# Artemis_Charger_Mod_PCB_2.net
KiCad netlist of a schematic drawn in EAGLE
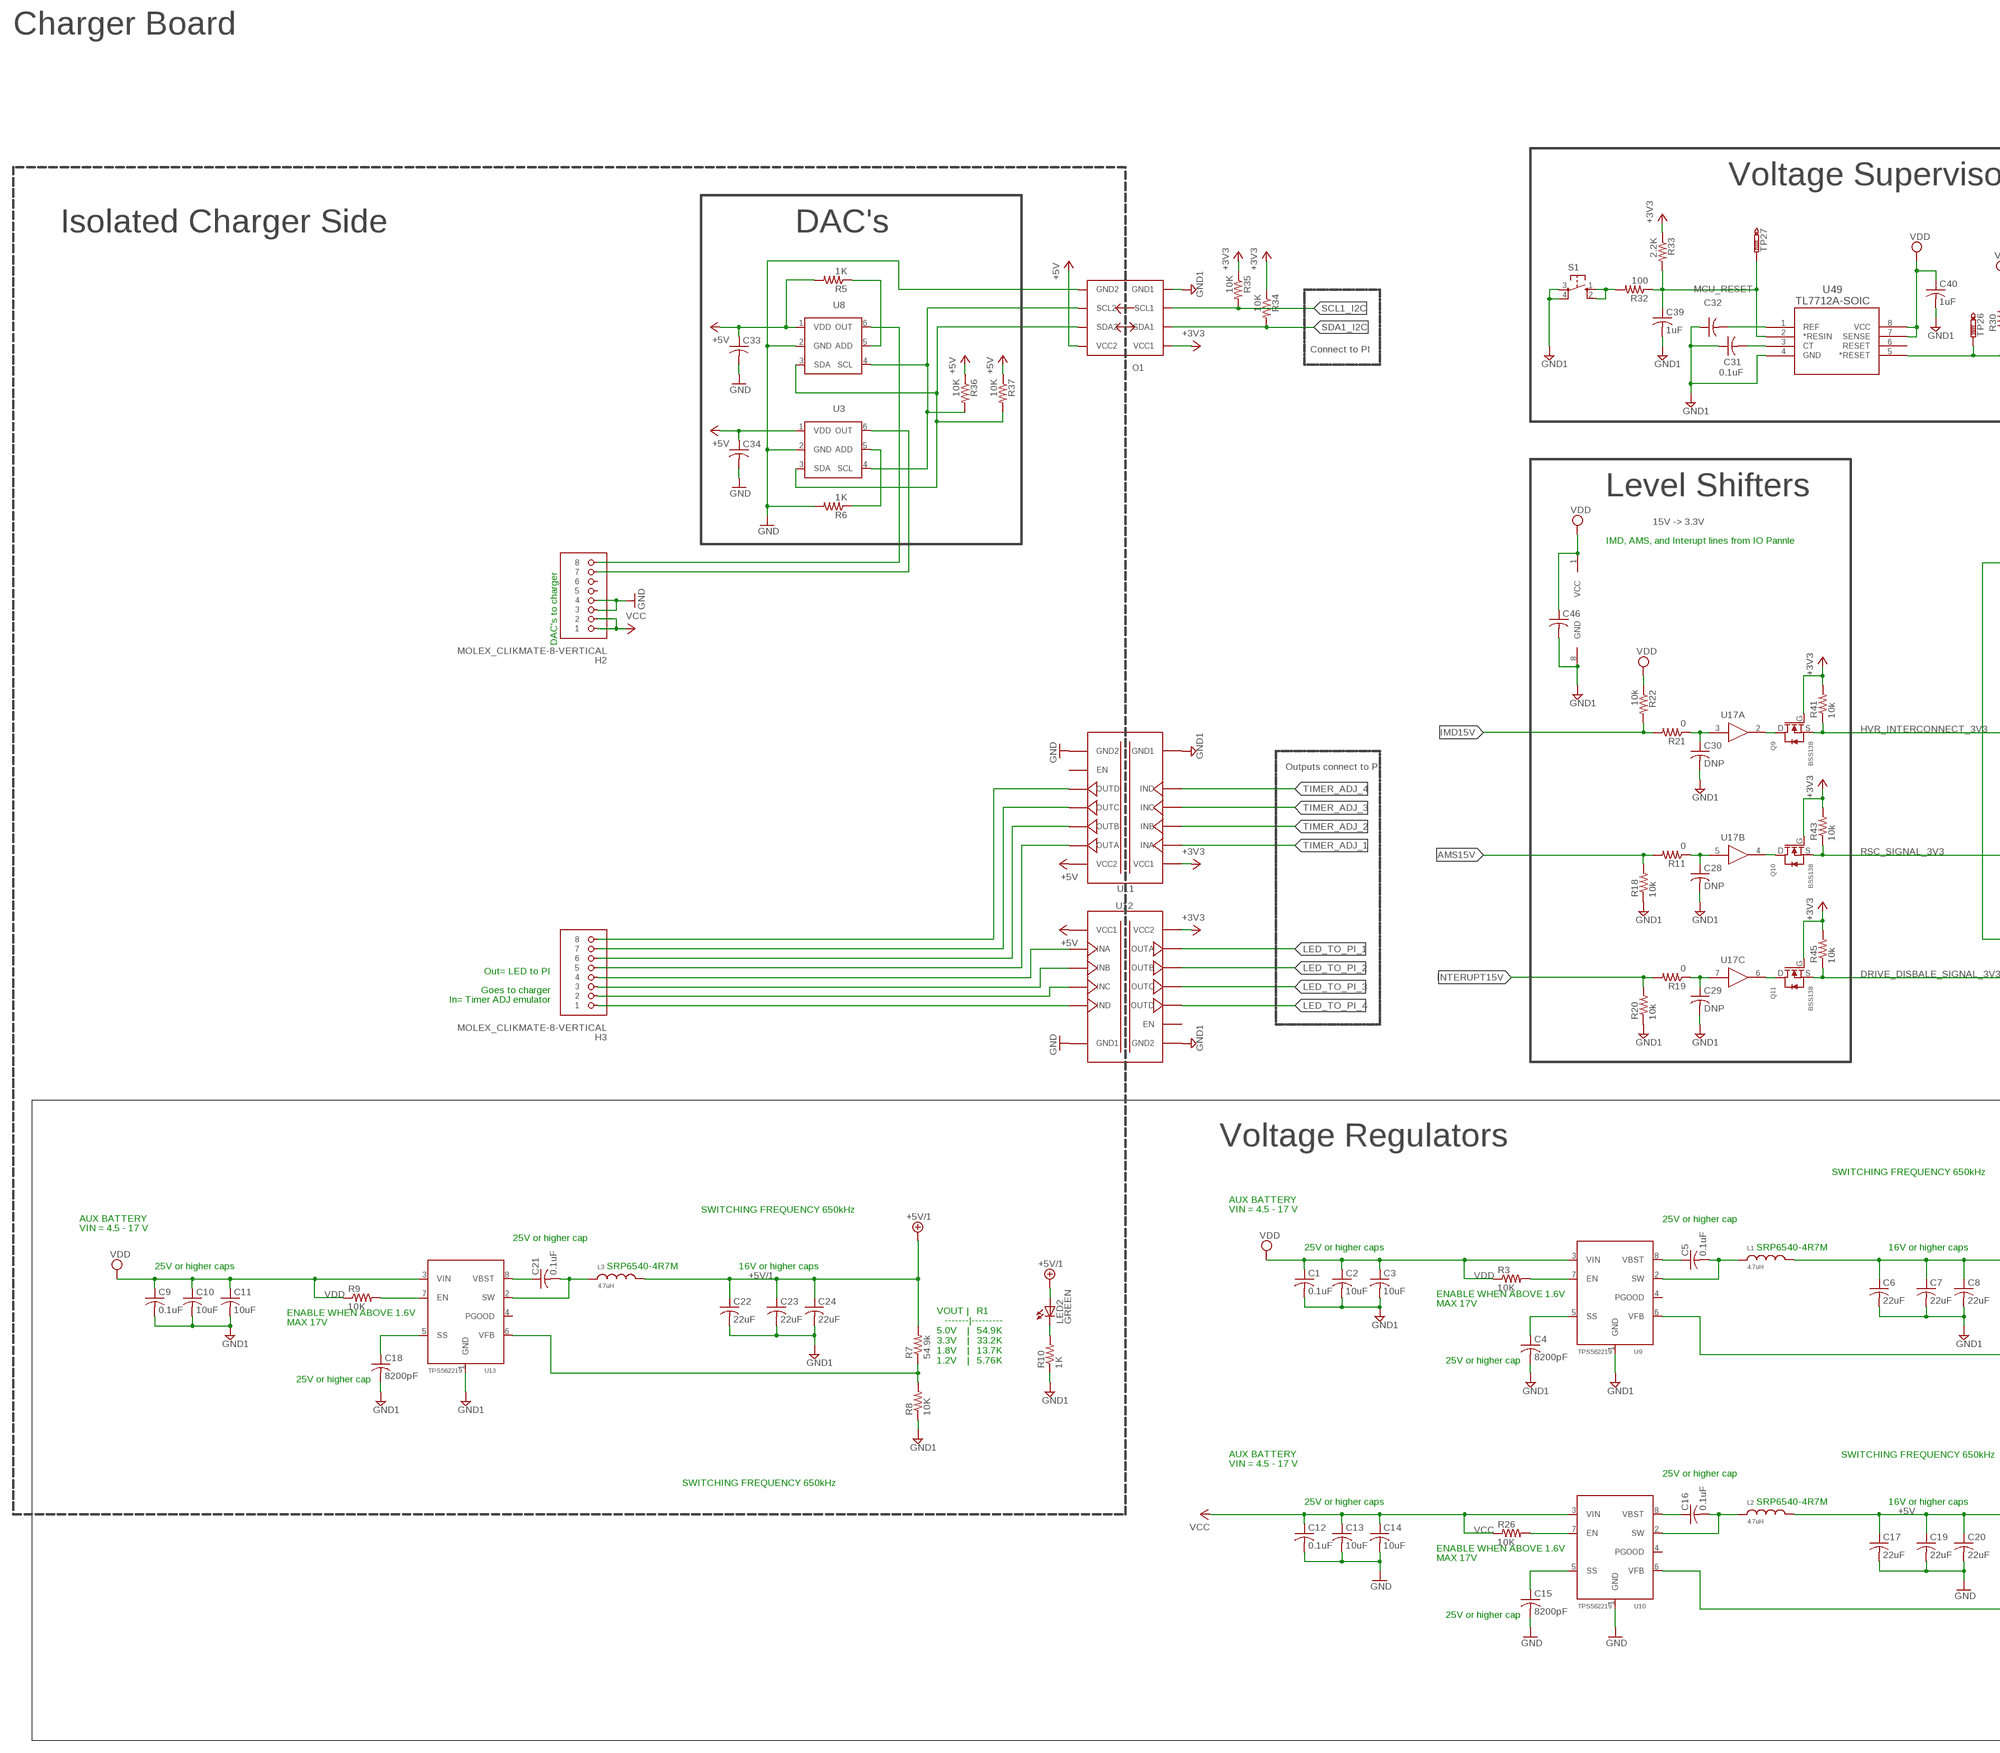
[diagram p0: schematic, sheet 1, part 1 of 2]
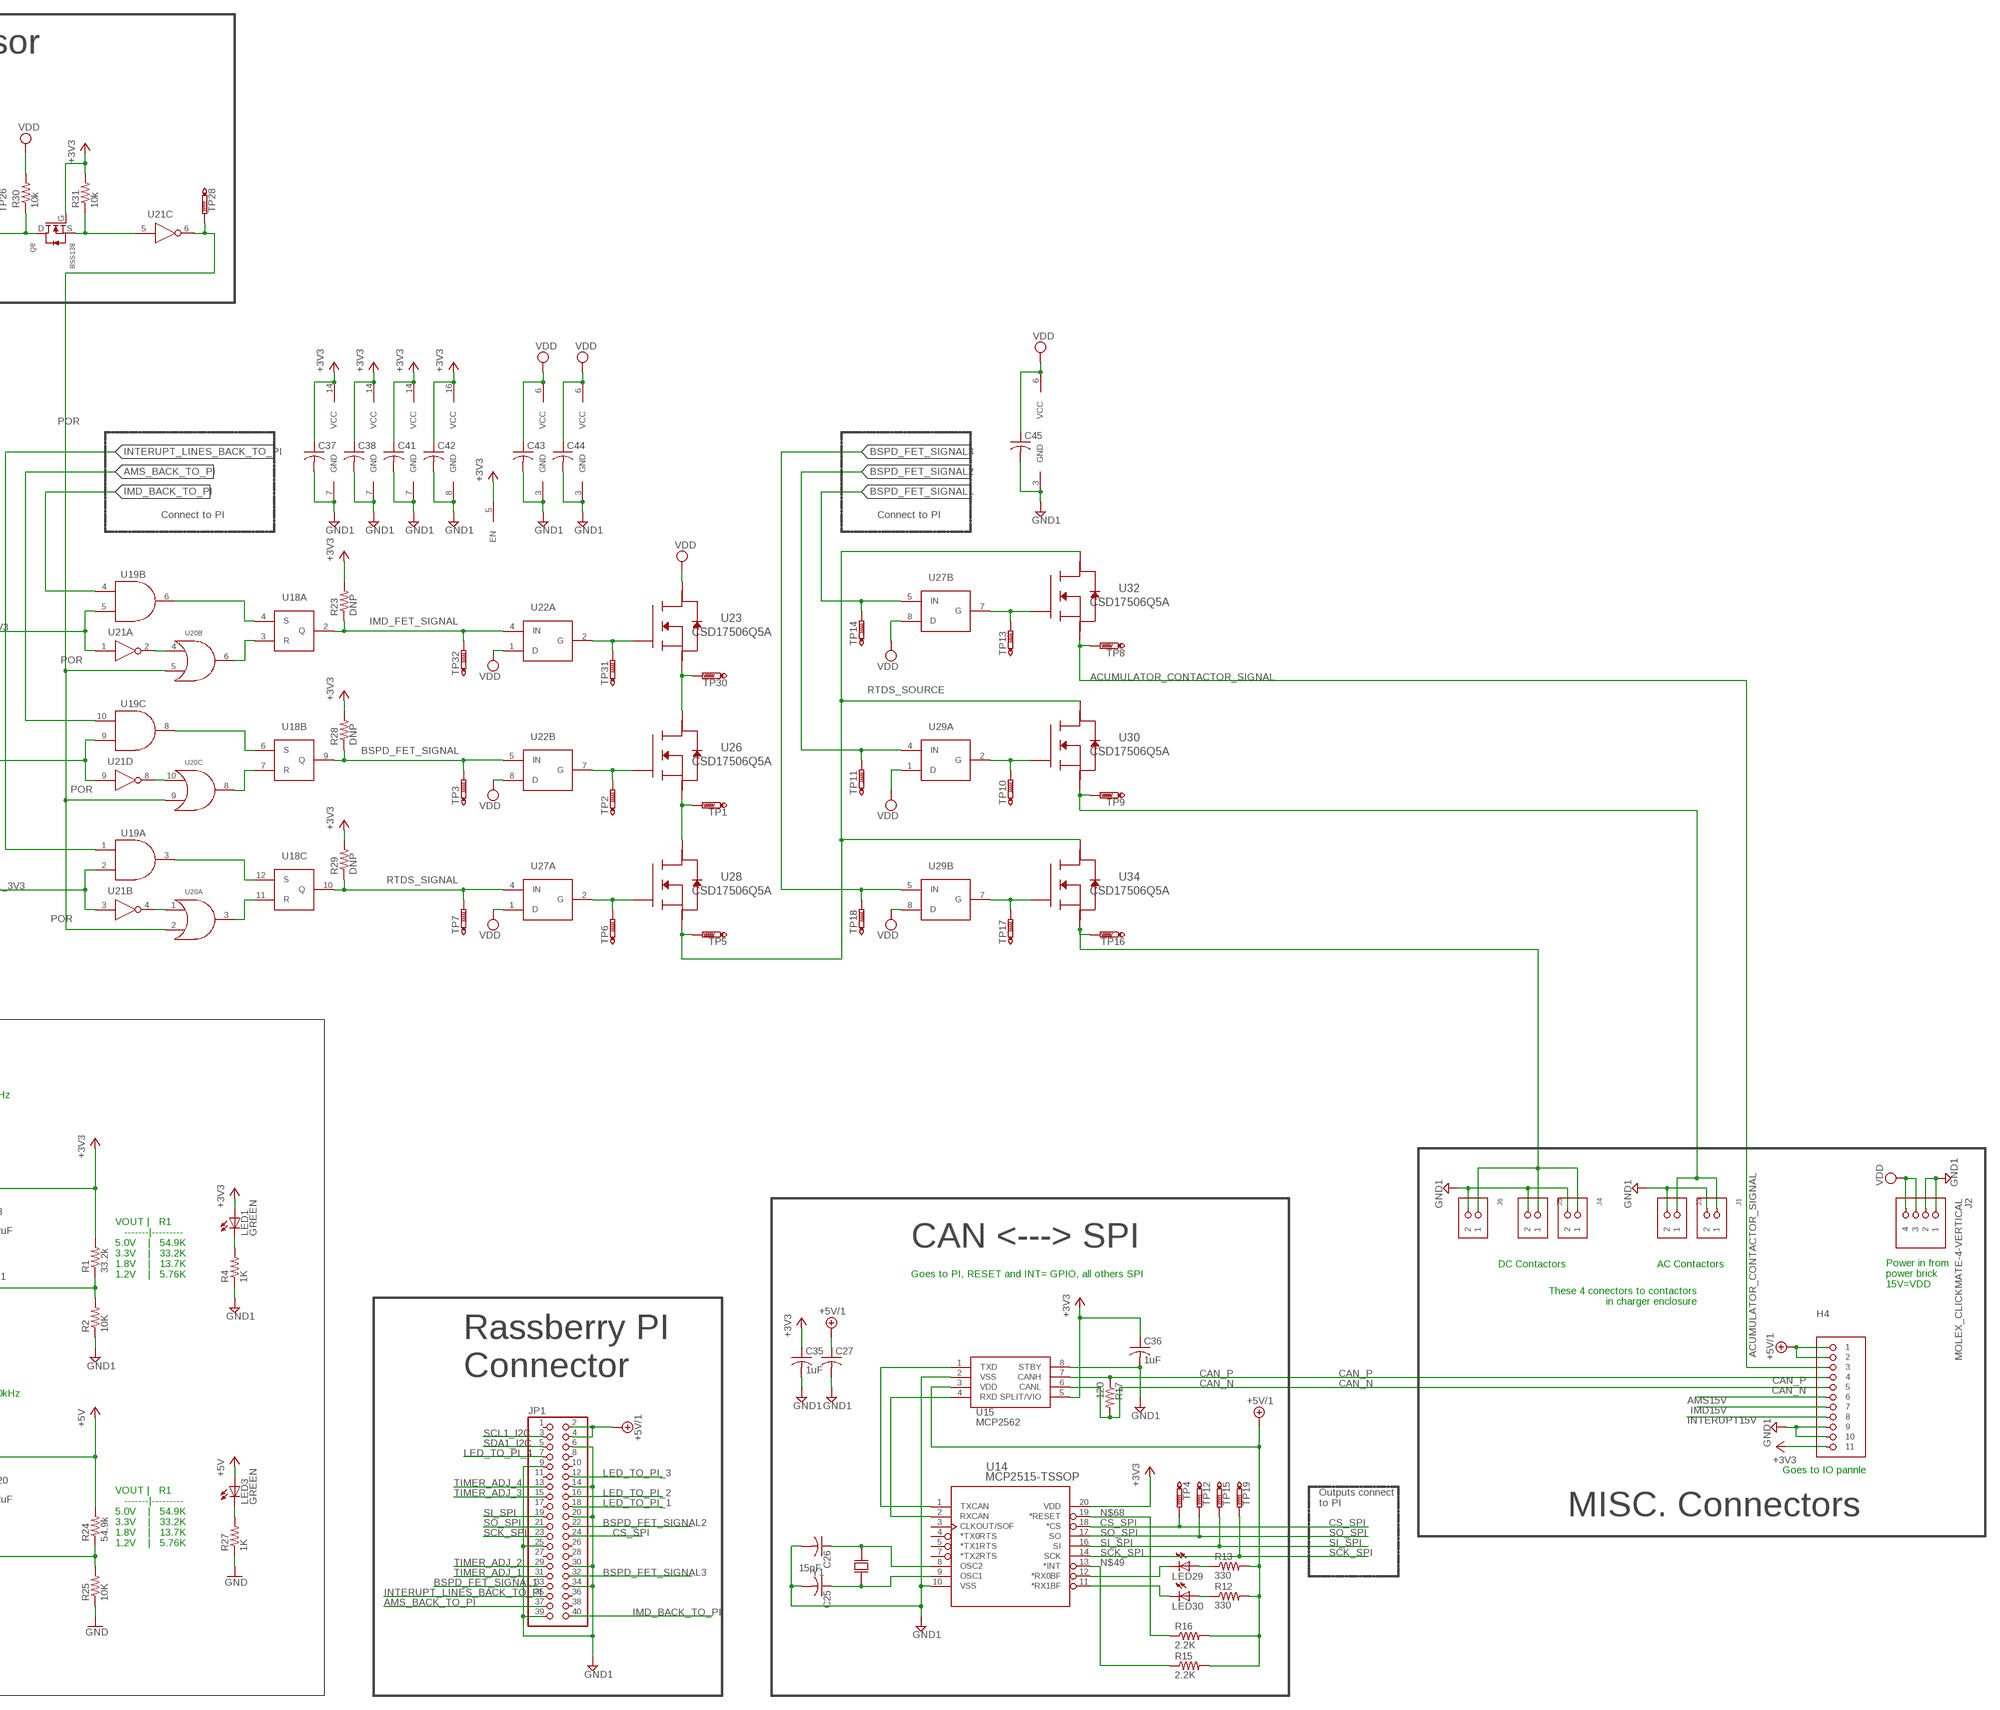
[diagram p1: schematic, sheet 1, part 2 of 2]

(export (version "E")
  (design (tool "Eeschema 10.0.6"))
  (components
    (comp (ref "C1")
      (value "0.1uF")
      (footprint "eagle-import:C0805")
      (fields (field (name "PARTNO") "GRM21BR71E104KA01L"))
      (libsource (lib "eagle-import") (part "C-USC0805"))
    )
    (comp (ref "C2")
      (value "10uF")
      (footprint "eagle-import:C0805")
      (fields (field (name "PARTNO") "GRM21BR61E106KA73L"))
      (libsource (lib "eagle-import") (part "C-USC0805"))
    )
    (comp (ref "C3")
      (value "10uF")
      (footprint "eagle-import:C0805")
      (fields (field (name "PARTNO") "GRM21BR61E106KA73L"))
      (libsource (lib "eagle-import") (part "C-USC0805"))
    )
    (comp (ref "C4")
      (value "8200pF")
      (footprint "eagle-import:C0805")
      (fields (field (name "PARTNO") "C0805C822K5RACTU"))
      (libsource (lib "eagle-import") (part "C-USC0805"))
    )
    (comp (ref "C5")
      (value "0.1uF")
      (footprint "eagle-import:C0805")
      (fields (field (name "PARTNO") "GRM21BR71E104KA01L"))
      (libsource (lib "eagle-import") (part "C-USC0805"))
    )
    (comp (ref "C6")
      (value "22uF")
      (footprint "eagle-import:C0805")
      (fields (field (name "PARTNO") "C2012JB1E226M125AC"))
      (libsource (lib "eagle-import") (part "C-USC0805"))
    )
    (comp (ref "C7")
      (value "22uF")
      (footprint "eagle-import:C0805")
      (fields (field (name "PARTNO") "C2012JB1E226M125AC"))
      (libsource (lib "eagle-import") (part "C-USC0805"))
    )
    (comp (ref "C8")
      (value "22uF")
      (footprint "eagle-import:C0805")
      (fields (field (name "PARTNO") "C2012JB1E226M125AC"))
      (libsource (lib "eagle-import") (part "C-USC0805"))
    )
    (comp (ref "C9")
      (value "0.1uF")
      (footprint "eagle-import:C0805")
      (fields (field (name "PARTNO") "5025841170"))
      (libsource (lib "eagle-import") (part "C-USC0805"))
    )
    (comp (ref "C10")
      (value "10uF")
      (footprint "eagle-import:C0805")
      (fields (field (name "PARTNO") "GRM21BR61E106KA73L"))
      (libsource (lib "eagle-import") (part "C-USC0805"))
    )
    (comp (ref "C11")
      (value "10uF")
      (footprint "eagle-import:C0805")
      (fields (field (name "PARTNO") "GRM21BR61E106KA73L"))
      (libsource (lib "eagle-import") (part "C-USC0805"))
    )
    (comp (ref "C12")
      (value "0.1uF")
      (footprint "eagle-import:C0805")
      (fields (field (name "PARTNO") "GRM21BR71E104KA01L"))
      (libsource (lib "eagle-import") (part "C-USC0805"))
    )
    (comp (ref "C13")
      (value "10uF")
      (footprint "eagle-import:C0805")
      (fields (field (name "PARTNO") "GRM21BR61E106KA73L"))
      (libsource (lib "eagle-import") (part "C-USC0805"))
    )
    (comp (ref "C14")
      (value "10uF")
      (footprint "eagle-import:C0805")
      (fields (field (name "PARTNO") "GRM21BR61E106KA73L"))
      (libsource (lib "eagle-import") (part "C-USC0805"))
    )
    (comp (ref "C15")
      (value "8200pF")
      (footprint "eagle-import:C0805")
      (fields (field (name "PARTNO") "C0805C822K5RACTU"))
      (libsource (lib "eagle-import") (part "C-USC0805"))
    )
    (comp (ref "C16")
      (value "0.1uF")
      (footprint "eagle-import:C0805")
      (fields (field (name "PARTNO") "GRM21BR71E104KA01L"))
      (libsource (lib "eagle-import") (part "C-USC0805"))
    )
    (comp (ref "C17")
      (value "22uF")
      (footprint "eagle-import:C0805")
      (fields (field (name "PARTNO") "C2012JB1E226M125AC"))
      (libsource (lib "eagle-import") (part "C-USC0805"))
    )
    (comp (ref "C18")
      (value "8200pF")
      (footprint "eagle-import:C0805")
      (fields (field (name "PARTNO") "C0805C822K5RACTU"))
      (libsource (lib "eagle-import") (part "C-USC0805"))
    )
    (comp (ref "C19")
      (value "22uF")
      (footprint "eagle-import:C0805")
      (fields (field (name "PARTNO") "C2012JB1E226M125AC"))
      (libsource (lib "eagle-import") (part "C-USC0805"))
    )
    (comp (ref "C20")
      (value "22uF")
      (footprint "eagle-import:C0805")
      (fields (field (name "PARTNO") "C2012JB1E226M125AC"))
      (libsource (lib "eagle-import") (part "C-USC0805"))
    )
    (comp (ref "C21")
      (value "0.1uF")
      (footprint "eagle-import:C0805")
      (fields (field (name "PARTNO") "GRM21BR71E104KA01L"))
      (libsource (lib "eagle-import") (part "C-USC0805"))
    )
    (comp (ref "C22")
      (value "22uF")
      (footprint "eagle-import:C0805")
      (fields (field (name "PARTNO") "C2012JB1E226M125AC"))
      (libsource (lib "eagle-import") (part "C-USC0805"))
    )
    (comp (ref "C23")
      (value "22uF")
      (footprint "eagle-import:C0805")
      (fields (field (name "PARTNO") "C2012JB1E226M125AC"))
      (libsource (lib "eagle-import") (part "C-USC0805"))
    )
    (comp (ref "C24")
      (value "22uF")
      (footprint "eagle-import:C0805")
      (fields (field (name "PARTNO") "C2012JB1E226M125AC"))
      (libsource (lib "eagle-import") (part "C-USC0805"))
    )
    (comp (ref "C25")
      (value "15pF")
      (footprint "eagle-import:C0805")
      (fields (field (name "MPN") "08051A150JAT2A") (field (name "PARTNO") "CL21C150JBANNNC"))
      (libsource (lib "eagle-import") (part "rcl_C-USC0805"))
    )
    (comp (ref "C26")
      (value "15pF")
      (footprint "eagle-import:C0805")
      (fields (field (name "MPN") "08051A150JAT2A") (field (name "PARTNO") "CL21C150JBANNNC"))
      (libsource (lib "eagle-import") (part "rcl_C-USC0805"))
    )
    (comp (ref "C27")
      (value "0.1uF")
      (footprint "eagle-import:C0805")
      (fields (field (name "MPN") "C1005X7R1E104K050BB") (field (name "PARTNO") "GRM21BR71E104KA01L"))
      (libsource (lib "eagle-import") (part "rcl_C-USC0805"))
    )
    (comp (ref "C28")
      (value "DNP")
      (footprint "eagle-import:C0805")
      (libsource (lib "eagle-import") (part "rcl_C-USC0805"))
    )
    (comp (ref "C29")
      (value "DNP")
      (footprint "eagle-import:C0805")
      (libsource (lib "eagle-import") (part "rcl_C-USC0805"))
    )
    (comp (ref "C30")
      (value "DNP")
      (footprint "eagle-import:C0805")
      (libsource (lib "eagle-import") (part "rcl_C-USC0805"))
    )
    (comp (ref "C31")
      (value "0.1uF")
      (footprint "eagle-import:C0805")
      (fields (field (name "MPN") "C2012X7R1H104K085AA") (field (name "PARTNO") "GRM21BR71E104KA01L"))
      (libsource (lib "eagle-import") (part "C-USC0805"))
    )
    (comp (ref "C32")
      (value "0.1uF")
      (footprint "eagle-import:C0805")
      (fields (field (name "MPN") "C2012X7R1H104K085AA") (field (name "PARTNO") "GRM21BR71E104KA01L"))
      (libsource (lib "eagle-import") (part "C-USC0805"))
    )
    (comp (ref "C33")
      (value "0.1uF")
      (footprint "eagle-import:C0805")
      (fields (field (name "MPN") "C1005X7R1E104K050BB") (field (name "PARTNO") "GRM21BR71E104KA01L"))
      (libsource (lib "eagle-import") (part "rcl_C-USC0805"))
    )
    (comp (ref "C34")
      (value "0.1uF")
      (footprint "eagle-import:C0805")
      (fields (field (name "MPN") "C1005X7R1E104K050BB") (field (name "PARTNO") "GRM21BR71E104KA01L"))
      (libsource (lib "eagle-import") (part "rcl_C-USC0805"))
    )
    (comp (ref "C35")
      (value "1uF")
      (footprint "eagle-import:C0805")
      (fields (field (name "PARTNO") "EMK212B7105KG-T"))
      (libsource (lib "eagle-import") (part "rcl_C-USC0805"))
    )
    (comp (ref "C36")
      (value "1uF")
      (footprint "eagle-import:C0805")
      (fields (field (name "PARTNO") "EMK212B7105KG-T"))
      (libsource (lib "eagle-import") (part "rcl_C-USC0805"))
    )
    (comp (ref "C37")
      (value "0.1uF")
      (footprint "eagle-import:C0805")
      (fields (field (name "MPN") "C1005X7R1E104K050BB") (field (name "PARTNO") "GRM21BR71E104KA01L"))
      (libsource (lib "eagle-import") (part "rcl_C-USC0805"))
    )
    (comp (ref "C38")
      (value "0.1uF")
      (footprint "eagle-import:C0805")
      (fields (field (name "MPN") "C1005X7R1E104K050BB") (field (name "PARTNO") "GRM21BR71E104KA01L"))
      (libsource (lib "eagle-import") (part "rcl_C-USC0805"))
    )
    (comp (ref "C39")
      (value "1uF")
      (footprint "eagle-import:C0805")
      (fields (field (name "PARTNO") "EMK212B7105KG-T"))
      (libsource (lib "eagle-import") (part "rcl_C-USC0805"))
    )
    (comp (ref "C40")
      (value "1uF")
      (footprint "eagle-import:C0805")
      (fields (field (name "PARTNO") "EMK212B7105KG-T"))
      (libsource (lib "eagle-import") (part "rcl_C-USC0805"))
    )
    (comp (ref "C41")
      (value "0.1uF")
      (footprint "eagle-import:C0805")
      (fields (field (name "MPN") "C1005X7R1E104K050BB") (field (name "PARTNO") "GRM21BR71E104KA01L"))
      (libsource (lib "eagle-import") (part "rcl_C-USC0805"))
    )
    (comp (ref "C42")
      (value "0.1uF")
      (footprint "eagle-import:C0805")
      (fields (field (name "MPN") "C1005X7R1E104K050BB") (field (name "PARTNO") "GRM21BR71E104KA01L"))
      (libsource (lib "eagle-import") (part "rcl_C-USC0805"))
    )
    (comp (ref "C43")
      (value "0.1uF")
      (footprint "eagle-import:C0805")
      (fields (field (name "MPN") "C1005X7R1E104K050BB") (field (name "PARTNO") "GRM21BR71E104KA01L"))
      (libsource (lib "eagle-import") (part "rcl_C-USC0805"))
    )
    (comp (ref "C44")
      (value "0.1uF")
      (footprint "eagle-import:C0805")
      (fields (field (name "MPN") "C1005X7R1E104K050BB") (field (name "PARTNO") "GRM21BR71E104KA01L"))
      (libsource (lib "eagle-import") (part "rcl_C-USC0805"))
    )
    (comp (ref "C45")
      (value "0.1uF")
      (footprint "eagle-import:C0805")
      (fields (field (name "MPN") "C1005X7R1E104K050BB") (field (name "PARTNO") "GRM21BR71E104KA01L"))
      (libsource (lib "eagle-import") (part "rcl_C-USC0805"))
    )
    (comp (ref "C46")
      (value "0.1uF")
      (footprint "eagle-import:C0805")
      (fields (field (name "MPN") "C1005X7R1E104K050BB") (field (name "PARTNO") "GRM21BR71E104KA01L"))
      (libsource (lib "eagle-import") (part "rcl_C-USC0805"))
    )
    (comp (ref "H2")
      (value "MOLEX_CLIKMATE-8-VERTICAL")
      (footprint "eagle-import:MOLEX-CLIKMATE-8-VERTICAL-HEADER")
      (fields (field (name "PARTNO") "5025840870"))
      (libsource (lib "eagle-import") (part "MOLEX_CLIKMATE-8-VERTICAL"))
    )
    (comp (ref "H3")
      (value "MOLEX_CLIKMATE-8-VERTICAL")
      (footprint "eagle-import:MOLEX-CLIKMATE-8-VERTICAL-HEADER")
      (fields (field (name "PARTNO") "5025840870"))
      (libsource (lib "eagle-import") (part "MOLEX_CLIKMATE-8-VERTICAL"))
    )
    (comp (ref "H4")
      (value "MOLEX_CLICKMATE-11-VERTICAL-VERTICAL")
      (footprint "eagle-import:MOLEX_CLICKMATE-11-VERTICAL-HEADER")
      (fields (field (name "PARTNO") "5025841170"))
      (libsource (lib "eagle-import") (part "MOLEX_CLICKMATE-11-VERTICAL-VERTICAL"))
    )
    (comp (ref "J1")
      (value "MOLEX_CLICKMATE-2-VERTICAL")
      (footprint "eagle-import:MOLEX-CLIKMATE-2-VERTICAL-HEADER")
      (fields (field (name "PARTNO") "5025840270"))
      (libsource (lib "eagle-import") (part "MOLEX_CLICKMATE-2-VERTICAL"))
    )
    (comp (ref "J2")
      (value "MOLEX_CLICKMATE-4-VERTICAL")
      (footprint "eagle-import:MOLEX-CLIKMATE-4-VERTICAL-HEADER")
      (fields (field (name "PARTNO") "5040500491"))
      (libsource (lib "eagle-import") (part "MOLEX_CLICKMATE-4-VERTICAL"))
    )
    (comp (ref "J3")
      (value "MOLEX_CLICKMATE-2-VERTICAL")
      (footprint "eagle-import:MOLEX-CLIKMATE-2-VERTICAL-HEADER")
      (fields (field (name "PARTNO") "5025840270"))
      (libsource (lib "eagle-import") (part "MOLEX_CLICKMATE-2-VERTICAL"))
    )
    (comp (ref "J4")
      (value "MOLEX_CLICKMATE-2-VERTICAL")
      (footprint "eagle-import:MOLEX-CLIKMATE-2-VERTICAL-HEADER")
      (fields (field (name "PARTNO") "5025840270"))
      (libsource (lib "eagle-import") (part "MOLEX_CLICKMATE-2-VERTICAL"))
    )
    (comp (ref "J5")
      (value "MOLEX_CLICKMATE-2-VERTICAL")
      (footprint "eagle-import:MOLEX-CLIKMATE-2-VERTICAL-HEADER")
      (fields (field (name "PARTNO") "5025840270"))
      (libsource (lib "eagle-import") (part "MOLEX_CLICKMATE-2-VERTICAL"))
    )
    (comp (ref "J6")
      (value "MOLEX_CLICKMATE-2-VERTICAL")
      (footprint "eagle-import:MOLEX-CLIKMATE-2-VERTICAL-HEADER")
      (fields (field (name "PARTNO") "5025840270"))
      (libsource (lib "eagle-import") (part "MOLEX_CLICKMATE-2-VERTICAL"))
    )
    (comp (ref "JP1")
      (value "PINHD-2X20")
      (footprint "eagle-import:2X20")
      (fields (field (name "PARTNO") "68602-220HLF"))
      (libsource (lib "eagle-import") (part "PINHD-2X20"))
    )
    (comp (ref "L1")
      (value "4.7uH")
      (footprint "eagle-import:SRP6540")
      (fields (field (name "PARTNO") "SRP6540-4R7M"))
      (libsource (lib "eagle-import") (part "SRP6540"))
    )
    (comp (ref "L2")
      (value "4.7uH")
      (footprint "eagle-import:SRP6540")
      (fields (field (name "PARTNO") "SRP6540-4R7M"))
      (libsource (lib "eagle-import") (part "SRP6540"))
    )
    (comp (ref "L3")
      (value "4.7uH")
      (footprint "eagle-import:SRP6540")
      (fields (field (name "PARTNO") "SRP6540-4R7M"))
      (libsource (lib "eagle-import") (part "SRP6540"))
    )
    (comp (ref "LED1")
      (value "GREEN")
      (footprint "eagle-import:CHIPLED_0805")
      (fields (field (name "PARTNO") "598-8170-107F"))
      (libsource (lib "eagle-import") (part "LEDCHIPLED_0805"))
    )
    (comp (ref "LED2")
      (value "GREEN")
      (footprint "eagle-import:CHIPLED_0805")
      (fields (field (name "PARTNO") "598-8170-107F"))
      (libsource (lib "eagle-import") (part "LEDCHIPLED_0805"))
    )
    (comp (ref "LED3")
      (value "GREEN")
      (footprint "eagle-import:CHIPLED_0805")
      (fields (field (name "PARTNO") "598-8170-107F"))
      (libsource (lib "eagle-import") (part "LEDCHIPLED_0805"))
    )
    (comp (ref "LED29")
      (value "LEDCHIP-LED0805")
      (footprint "eagle-import:CHIP-LED0805")
      (fields (field (name "PARTNO") "598-8170-107F"))
      (libsource (lib "eagle-import") (part "adafruit_LEDCHIP-LED0805"))
    )
    (comp (ref "LED30")
      (value "LEDCHIP-LED0805")
      (footprint "eagle-import:CHIP-LED0805")
      (fields (field (name "PARTNO") "598-8170-107F"))
      (libsource (lib "eagle-import") (part "adafruit_LEDCHIP-LED0805"))
    )
    (comp (ref "O1")
      (value "ISO1541")
      (footprint "eagle-import:ISO1541")
      (fields (field (name "PARTNO") "ISO1541DR"))
      (libsource (lib "eagle-import") (part "ISO1541"))
    )
    (comp (ref "Q8")
      (value "BSS138")
      (footprint "eagle-import:BSS138")
      (libsource (lib "eagle-import") (part "BSS138"))
    )
    (comp (ref "Q9")
      (value "BSS138")
      (footprint "eagle-import:BSS138")
      (libsource (lib "eagle-import") (part "BSS138"))
    )
    (comp (ref "Q10")
      (value "BSS138")
      (footprint "eagle-import:BSS138")
      (libsource (lib "eagle-import") (part "BSS138"))
    )
    (comp (ref "Q11")
      (value "BSS138")
      (footprint "eagle-import:BSS138")
      (libsource (lib "eagle-import") (part "BSS138"))
    )
    (comp (ref "R1")
      (value "33.2k")
      (footprint "eagle-import:R0805")
      (fields (field (name "PARTNO") "1676307-2"))
      (libsource (lib "eagle-import") (part "R-US_R0805"))
    )
    (comp (ref "R2")
      (value "10K")
      (footprint "eagle-import:R0805")
      (fields (field (name "PARTNO") "ERJ-6ENF1002V"))
      (libsource (lib "eagle-import") (part "R-US_R0805"))
    )
    (comp (ref "R3")
      (value "10K")
      (footprint "eagle-import:R0805")
      (fields (field (name "PARTNO") "ERJ-6ENF1002V"))
      (libsource (lib "eagle-import") (part "R-US_R0805"))
    )
    (comp (ref "R4")
      (value "1K")
      (footprint "eagle-import:R0805")
      (fields (field (name "PARTNO") "ERJ-6ENF1001V"))
      (libsource (lib "eagle-import") (part "R-US_R0805"))
    )
    (comp (ref "R5")
      (value "1K")
      (footprint "eagle-import:R0805")
      (fields (field (name "PARTNO") "ERJ-6ENF1001V"))
      (libsource (lib "eagle-import") (part "R-US_R0805"))
    )
    (comp (ref "R6")
      (value "1K")
      (footprint "eagle-import:R0805")
      (fields (field (name "PARTNO") "ERJ-6ENF1001V"))
      (libsource (lib "eagle-import") (part "R-US_R0805"))
    )
    (comp (ref "R7")
      (value "54.9k")
      (footprint "eagle-import:R0805")
      (fields (field (name "PARTNO") "ERA-6AEB5492V"))
      (libsource (lib "eagle-import") (part "R-US_R0805"))
    )
    (comp (ref "R8")
      (value "10K")
      (footprint "eagle-import:R0805")
      (fields (field (name "PARTNO") "ERJ-6ENF1002V"))
      (libsource (lib "eagle-import") (part "R-US_R0805"))
    )
    (comp (ref "R9")
      (value "10K")
      (footprint "eagle-import:R0805")
      (fields (field (name "PARTNO") "ERJ-6ENF1002V"))
      (libsource (lib "eagle-import") (part "R-US_R0805"))
    )
    (comp (ref "R10")
      (value "1K")
      (footprint "eagle-import:R0805")
      (fields (field (name "PARTNO") "ERJ-6ENF1001V"))
      (libsource (lib "eagle-import") (part "R-US_R0805"))
    )
    (comp (ref "R11")
      (value "0")
      (footprint "eagle-import:R0805")
      (fields (field (name "PARTNO") "ERJ-6GEY0R00V"))
      (libsource (lib "eagle-import") (part "rcl_R-US_R0805"))
    )
    (comp (ref "R12")
      (value "330")
      (footprint "eagle-import:R0805")
      (fields (field (name "PARTNO") "ERJ-P6WF3300V"))
      (libsource (lib "eagle-import") (part "R-US_R0805"))
    )
    (comp (ref "R13")
      (value "330")
      (footprint "eagle-import:R0805")
      (fields (field (name "PARTNO") "ERJ-P6WF3300V"))
      (libsource (lib "eagle-import") (part "R-US_R0805"))
    )
    (comp (ref "R15")
      (value "2.2K")
      (footprint "eagle-import:R0805")
      (fields (field (name "PARTNO") "ERA-6AEB222V"))
      (libsource (lib "eagle-import") (part "R-US_R0805"))
    )
    (comp (ref "R16")
      (value "2.2K")
      (footprint "eagle-import:R0805")
      (fields (field (name "PARTNO") "ERA-6AEB222V"))
      (libsource (lib "eagle-import") (part "R-US_R0805"))
    )
    (comp (ref "R17")
      (value "120")
      (footprint "eagle-import:R0805")
      (fields (field (name "PARTNO") "ERJ-6ENF1200V"))
      (libsource (lib "eagle-import") (part "R-US_R0805"))
    )
    (comp (ref "R18")
      (value "10k")
      (footprint "eagle-import:R0805")
      (fields (field (name "PARTNO") "ERJ-6ENF1002V"))
      (libsource (lib "eagle-import") (part "rcl_R-US_R0805"))
    )
    (comp (ref "R19")
      (value "0")
      (footprint "eagle-import:R0805")
      (fields (field (name "PARTNO") "ERJ-6GEY0R00V"))
      (libsource (lib "eagle-import") (part "rcl_R-US_R0805"))
    )
    (comp (ref "R20")
      (value "10k")
      (footprint "eagle-import:R0805")
      (fields (field (name "PARTNO") "ERJ-6ENF1002V"))
      (libsource (lib "eagle-import") (part "rcl_R-US_R0805"))
    )
    (comp (ref "R21")
      (value "0")
      (footprint "eagle-import:R0805")
      (fields (field (name "PARTNO") "ERJ-6GEY0R00V"))
      (libsource (lib "eagle-import") (part "rcl_R-US_R0805"))
    )
    (comp (ref "R22")
      (value "10k")
      (footprint "eagle-import:R0805")
      (fields (field (name "PARTNO") "ERJ-6ENF1002V"))
      (libsource (lib "eagle-import") (part "rcl_R-US_R0805"))
    )
    (comp (ref "R23")
      (value "DNP")
      (footprint "eagle-import:R0805")
      (libsource (lib "eagle-import") (part "rcl_R-US_R0805"))
    )
    (comp (ref "R24")
      (value "54.9k")
      (footprint "eagle-import:R0805")
      (fields (field (name "PARTNO") "ERA-6AEB5492V"))
      (libsource (lib "eagle-import") (part "R-US_R0805"))
    )
    (comp (ref "R25")
      (value "10K")
      (footprint "eagle-import:R0805")
      (fields (field (name "PARTNO") "ERJ-6ENF1002V"))
      (libsource (lib "eagle-import") (part "R-US_R0805"))
    )
    (comp (ref "R26")
      (value "10K")
      (footprint "eagle-import:R0805")
      (fields (field (name "PARTNO") "ERJ-6ENF1002V"))
      (libsource (lib "eagle-import") (part "R-US_R0805"))
    )
    (comp (ref "R27")
      (value "1K")
      (footprint "eagle-import:R0805")
      (fields (field (name "PARTNO") "ERJ-6ENF1001V"))
      (libsource (lib "eagle-import") (part "R-US_R0805"))
    )
    (comp (ref "R28")
      (value "DNP")
      (footprint "eagle-import:R0805")
      (libsource (lib "eagle-import") (part "rcl_R-US_R0805"))
    )
    (comp (ref "R29")
      (value "DNP")
      (footprint "eagle-import:R0805")
      (libsource (lib "eagle-import") (part "rcl_R-US_R0805"))
    )
    (comp (ref "R30")
      (value "10k")
      (footprint "eagle-import:R0805")
      (fields (field (name "PARTNO") "ERJ-6ENF1002V"))
      (libsource (lib "eagle-import") (part "rcl_R-US_R0805"))
    )
    (comp (ref "R31")
      (value "10k")
      (footprint "eagle-import:R0805")
      (fields (field (name "PARTNO") "ERJ-6ENF1002V"))
      (libsource (lib "eagle-import") (part "rcl_R-US_R0805"))
    )
    (comp (ref "R32")
      (value "100")
      (footprint "eagle-import:R0805")
      (fields (field (name "PARTNO") "ERJ-6ENF1000V"))
      (libsource (lib "eagle-import") (part "rcl_R-US_R0805"))
    )
    (comp (ref "R33")
      (value "2.2K")
      (footprint "eagle-import:R0805")
      (fields (field (name "PARTNO") "ERA-6AEB222V"))
      (libsource (lib "eagle-import") (part "rcl_R-US_R0805"))
    )
    (comp (ref "R34")
      (value "10K")
      (footprint "eagle-import:R0805")
      (fields (field (name "PARTNO") "ERJ-6ENF1002V"))
      (libsource (lib "eagle-import") (part "R-US_R0805"))
    )
    (comp (ref "R35")
      (value "10K")
      (footprint "eagle-import:R0805")
      (fields (field (name "PARTNO") "ERJ-6ENF1002V"))
      (libsource (lib "eagle-import") (part "R-US_R0805"))
    )
    (comp (ref "R36")
      (value "10K")
      (footprint "eagle-import:R0805")
      (fields (field (name "PARTNO") "ERJ-6ENF1002V"))
      (libsource (lib "eagle-import") (part "R-US_R0805"))
    )
    (comp (ref "R37")
      (value "10K")
      (footprint "eagle-import:R0805")
      (fields (field (name "PARTNO") "ERJ-6ENF1002V"))
      (libsource (lib "eagle-import") (part "R-US_R0805"))
    )
    (comp (ref "R41")
      (value "10k")
      (footprint "eagle-import:R0805")
      (fields (field (name "PARTNO") "ERJ-6ENF1002V"))
      (libsource (lib "eagle-import") (part "rcl_R-US_R0805"))
    )
    (comp (ref "R43")
      (value "10k")
      (footprint "eagle-import:R0805")
      (fields (field (name "PARTNO") "ERJ-6ENF1002V"))
      (libsource (lib "eagle-import") (part "rcl_R-US_R0805"))
    )
    (comp (ref "R45")
      (value "10k")
      (footprint "eagle-import:R0805")
      (fields (field (name "PARTNO") "ERJ-6ENF1002V"))
      (libsource (lib "eagle-import") (part "rcl_R-US_R0805"))
    )
    (comp (ref "S1")
      (value "TE-FSM4JSMATR")
      (footprint "eagle-import:TE-FSM4JSMATR")
      (fields (field (name "PARTNO") "FSM4JSMATR"))
      (libsource (lib "eagle-import") (part "TE-FSM4JSMATR"))
    )
    (comp (ref "TP1")
      (value "PTR1TP20R")
      (footprint "eagle-import:TP20R")
      (libsource (lib "eagle-import") (part "PTR1TP20R"))
    )
    (comp (ref "TP2")
      (value "PTR1TP20R")
      (footprint "eagle-import:TP20R")
      (libsource (lib "eagle-import") (part "PTR1TP20R"))
    )
    (comp (ref "TP3")
      (value "PTR1TP20R")
      (footprint "eagle-import:TP20R")
      (libsource (lib "eagle-import") (part "PTR1TP20R"))
    )
    (comp (ref "TP4")
      (value "PTR1TP20R")
      (footprint "eagle-import:TP20R")
      (libsource (lib "eagle-import") (part "PTR1TP20R"))
    )
    (comp (ref "TP5")
      (value "PTR1TP20R")
      (footprint "eagle-import:TP20R")
      (libsource (lib "eagle-import") (part "PTR1TP20R"))
    )
    (comp (ref "TP6")
      (value "PTR1TP20R")
      (footprint "eagle-import:TP20R")
      (libsource (lib "eagle-import") (part "PTR1TP20R"))
    )
    (comp (ref "TP7")
      (value "PTR1TP20R")
      (footprint "eagle-import:TP20R")
      (libsource (lib "eagle-import") (part "PTR1TP20R"))
    )
    (comp (ref "TP8")
      (value "PTR1TP20R")
      (footprint "eagle-import:TP20R")
      (libsource (lib "eagle-import") (part "PTR1TP20R"))
    )
    (comp (ref "TP9")
      (value "PTR1TP20R")
      (footprint "eagle-import:TP20R")
      (libsource (lib "eagle-import") (part "PTR1TP20R"))
    )
    (comp (ref "TP10")
      (value "PTR1TP20R")
      (footprint "eagle-import:TP20R")
      (libsource (lib "eagle-import") (part "PTR1TP20R"))
    )
    (comp (ref "TP11")
      (value "PTR1TP20R")
      (footprint "eagle-import:TP20R")
      (libsource (lib "eagle-import") (part "PTR1TP20R"))
    )
    (comp (ref "TP12")
      (value "PTR1TP20R")
      (footprint "eagle-import:TP20R")
      (libsource (lib "eagle-import") (part "PTR1TP20R"))
    )
    (comp (ref "TP13")
      (value "PTR1TP20R")
      (footprint "eagle-import:TP20R")
      (libsource (lib "eagle-import") (part "PTR1TP20R"))
    )
    (comp (ref "TP14")
      (value "PTR1TP20R")
      (footprint "eagle-import:TP20R")
      (libsource (lib "eagle-import") (part "PTR1TP20R"))
    )
    (comp (ref "TP15")
      (value "PTR1TP20R")
      (footprint "eagle-import:TP20R")
      (libsource (lib "eagle-import") (part "PTR1TP20R"))
    )
    (comp (ref "TP16")
      (value "PTR1TP20R")
      (footprint "eagle-import:TP20R")
      (libsource (lib "eagle-import") (part "PTR1TP20R"))
    )
    (comp (ref "TP17")
      (value "PTR1TP20R")
      (footprint "eagle-import:TP20R")
      (libsource (lib "eagle-import") (part "PTR1TP20R"))
    )
    (comp (ref "TP18")
      (value "PTR1TP20R")
      (footprint "eagle-import:TP20R")
      (libsource (lib "eagle-import") (part "PTR1TP20R"))
    )
    (comp (ref "TP19")
      (value "PTR1TP20R")
      (footprint "eagle-import:TP20R")
      (libsource (lib "eagle-import") (part "PTR1TP20R"))
    )
    (comp (ref "TP26")
      (value "PTR1TP20R")
      (footprint "eagle-import:TP20R")
      (libsource (lib "eagle-import") (part "PTR1TP20R"))
    )
    (comp (ref "TP27")
      (value "PTR1TP20R")
      (footprint "eagle-import:TP20R")
      (libsource (lib "eagle-import") (part "PTR1TP20R"))
    )
    (comp (ref "TP28")
      (value "PTR1TP20R")
      (footprint "eagle-import:TP20R")
      (libsource (lib "eagle-import") (part "PTR1TP20R"))
    )
    (comp (ref "TP30")
      (value "PTR1TP20R")
      (footprint "eagle-import:TP20R")
      (libsource (lib "eagle-import") (part "PTR1TP20R"))
    )
    (comp (ref "TP31")
      (value "PTR1TP20R")
      (footprint "eagle-import:TP20R")
      (libsource (lib "eagle-import") (part "PTR1TP20R"))
    )
    (comp (ref "TP32")
      (value "PTR1TP20R")
      (footprint "eagle-import:TP20R")
      (libsource (lib "eagle-import") (part "PTR1TP20R"))
    )
    (comp (ref "U3")
      (value "MAX5812LEUT+TCT-ND")
      (footprint "eagle-import:MAX5812")
      (fields (field (name "PARTNO") "MAX5812LEUT+T"))
      (libsource (lib "eagle-import") (part "MAX5812M"))
    )
    (comp (ref "U8")
      (value "MAX5812LEUT+TCT-ND")
      (footprint "eagle-import:MAX5812")
      (fields (field (name "PARTNO") "MAX5812LEUT+T"))
      (libsource (lib "eagle-import") (part "MAX5812M"))
    )
    (comp (ref "U9")
      (value "TPS562219")
      (footprint "eagle-import:TPS562219")
      (fields (field (name "PARTNO") "TPS562219DDFT"))
      (libsource (lib "eagle-import") (part "TPS562219"))
    )
    (comp (ref "U10")
      (value "TPS562219")
      (footprint "eagle-import:TPS562219")
      (fields (field (name "PARTNO") "TPS562219DDFT"))
      (libsource (lib "eagle-import") (part "TPS562219"))
    )
    (comp (ref "U11")
      (value "ISO7340")
      (footprint "eagle-import:ISO734X")
      (fields (field (name "PARTNO") "ISO7340CDWR"))
      (libsource (lib "eagle-import") (part "ISO7340"))
    )
    (comp (ref "U12")
      (value "ISO7340")
      (footprint "eagle-import:ISO734X")
      (fields (field (name "PARTNO") "ISO7340CDWR"))
      (libsource (lib "eagle-import") (part "ISO7340"))
    )
    (comp (ref "U13")
      (value "TPS562219")
      (footprint "eagle-import:TPS562219")
      (fields (field (name "PARTNO") "TPS562219DDFT"))
      (libsource (lib "eagle-import") (part "TPS562219"))
    )
    (comp (ref "U14")
      (value "MCP2515-TSSOP")
      (footprint "eagle-import:TSSOP20_MC")
      (fields (field (name "MPN") "MCP2515-E/ST"))
      (libsource (lib "eagle-import") (part "MCP2515-TSSOP"))
    )
    (comp (ref "U15")
      (value "MCP2562")
      (footprint "eagle-import:SOIC8-N_MC")
      (fields (field (name "MPN") "MCP2562-E/SN"))
      (libsource (lib "eagle-import") (part "MCP256X-SOIC"))
    )
    (comp (ref "U17")
      (value "CD4050BD")
      (footprint "eagle-import:SOIC-16")
      (fields (field (name "PARTNO") "CD4050BDR"))
      (libsource (lib "eagle-import") (part "CD4050BD"))
    )
    (comp (ref "U18")
      (value "CD4043B")
      (footprint "eagle-import:PW16-M")
      (fields (field (name "PARTNO") "CD4043BPWR"))
      (libsource (lib "eagle-import") (part "CD4043B"))
    )
    (comp (ref "U19")
      (value "SN74LVC08ASOIC")
      (footprint "eagle-import:D14")
      (fields (field (name "PARTNO") "SN74LVC08ADR"))
      (libsource (lib "eagle-import") (part "SN74LVC08ASOIC"))
    )
    (comp (ref "U20")
      (value "SN74LVC32ASOIC")
      (footprint "eagle-import:D14")
      (fields (field (name "PARTNO") "SN74LVC32ADR"))
      (libsource (lib "eagle-import") (part "SN74LVC32ASOIC"))
    )
    (comp (ref "U21")
      (value "SN74LVC04ASOIC")
      (footprint "eagle-import:SOIC-14")
      (fields (field (name "PARTNO") "SN74LVC04ADR"))
      (libsource (lib "eagle-import") (part "SN74LVC04ASOIC"))
    )
    (comp (ref "U22")
      (value "LTC1155")
      (footprint "eagle-import:LT-SOL8")
      (fields (field (name "PARTNO") "LTC1155CS8#PBF"))
      (libsource (lib "eagle-import") (part "LTC1155"))
    )
    (comp (ref "U23")
      (value "CSD17506Q5A")
      (footprint "eagle-import:SON_5X6")
      (libsource (lib "eagle-import") (part "CSD17506Q5A"))
    )
    (comp (ref "U26")
      (value "CSD17506Q5A")
      (footprint "eagle-import:SON_5X6")
      (libsource (lib "eagle-import") (part "CSD17506Q5A"))
    )
    (comp (ref "U27")
      (value "LTC1155")
      (footprint "eagle-import:LT-SOL8")
      (fields (field (name "PARTNO") "LTC1155CS8#PBF"))
      (libsource (lib "eagle-import") (part "LTC1155"))
    )
    (comp (ref "U28")
      (value "CSD17506Q5A")
      (footprint "eagle-import:SON_5X6")
      (libsource (lib "eagle-import") (part "CSD17506Q5A"))
    )
    (comp (ref "U29")
      (value "LTC1155")
      (footprint "eagle-import:LT-SOL8")
      (fields (field (name "PARTNO") "LTC1155CS8#PBF"))
      (libsource (lib "eagle-import") (part "LTC1155"))
    )
    (comp (ref "U30")
      (value "CSD17506Q5A")
      (footprint "eagle-import:SON_5X6")
      (libsource (lib "eagle-import") (part "CSD17506Q5A"))
    )
    (comp (ref "U32")
      (value "CSD17506Q5A")
      (footprint "eagle-import:SON_5X6")
      (libsource (lib "eagle-import") (part "CSD17506Q5A"))
    )
    (comp (ref "U34")
      (value "CSD17506Q5A")
      (footprint "eagle-import:SON_5X6")
      (libsource (lib "eagle-import") (part "CSD17506Q5A"))
    )
    (comp (ref "U49")
      (value "TL7712A-SOIC")
      (footprint "eagle-import:D8")
      (fields
        (field (name "GENERIC_PART_NUMBER") "TL7709A")
        (field (name "MANUFACTURER") "Texas Instruments")
        (field (name "MANUFACTURER_PART_NUMBER") "tl7705b_d_8")
      )
      (libsource (lib "eagle-import") (part "TL7709A-SOIC"))
    )
    (comp (ref "Y1")
      (value "CSM-3X")
      (footprint "eagle-import:CSM-3X")
      (fields (field (name "PARTNO") "ECS-160-20-3X-TR"))
      (libsource (lib "eagle-import") (part "CSM-3X"))
    )
  )
  (nets
    (net (code "1") (name "+3V3") (class "Default")
      (node (ref "C35") (pin "1") (pinfunction "1_1") (pintype "passive"))
      (node (ref "C36") (pin "1") (pinfunction "1_1") (pintype "passive"))
      (node (ref "C37") (pin "1") (pinfunction "1_1") (pintype "passive"))
      (node (ref "C38") (pin "1") (pinfunction "1_1") (pintype "passive"))
      (node (ref "C41") (pin "1") (pinfunction "1_1") (pintype "passive"))
      (node (ref "C42") (pin "1") (pinfunction "1_1") (pintype "passive"))
      (node (ref "C6") (pin "1") (pinfunction "1_1") (pintype "passive"))
      (node (ref "C7") (pin "1") (pinfunction "1_1") (pintype "passive"))
      (node (ref "C8") (pin "1") (pinfunction "1_1") (pintype "passive"))
      (node (ref "H4") (pin "11") (pinfunction "11_11") (pintype "bidirectional"))
      (node (ref "L1") (pin "P$2") (pinfunction "P$2_P$2") (pintype "bidirectional"))
      (node (ref "LED1") (pin "A") (pinfunction "A_A") (pintype "passive"))
      (node (ref "O1") (pin "1") (pinfunction "VCC1_1") (pintype "bidirectional"))
      (node (ref "Q10") (pin "G") (pinfunction "G_G") (pintype "bidirectional"))
      (node (ref "Q11") (pin "G") (pinfunction "G_G") (pintype "bidirectional"))
      (node (ref "Q8") (pin "G") (pinfunction "G_G") (pintype "bidirectional"))
      (node (ref "Q9") (pin "G") (pinfunction "G_G") (pintype "bidirectional"))
      (node (ref "R1") (pin "2") (pinfunction "2_2") (pintype "passive"))
      (node (ref "R23") (pin "2") (pinfunction "2_2") (pintype "passive"))
      (node (ref "R28") (pin "2") (pinfunction "2_2") (pintype "passive"))
      (node (ref "R29") (pin "2") (pinfunction "2_2") (pintype "passive"))
      (node (ref "R31") (pin "2") (pinfunction "2_2") (pintype "passive"))
      (node (ref "R33") (pin "1") (pinfunction "1_1") (pintype "passive"))
      (node (ref "R34") (pin "1") (pinfunction "1_1") (pintype "passive"))
      (node (ref "R35") (pin "1") (pinfunction "1_1") (pintype "passive"))
      (node (ref "R41") (pin "2") (pinfunction "2_2") (pintype "passive"))
      (node (ref "R43") (pin "2") (pinfunction "2_2") (pintype "passive"))
      (node (ref "R45") (pin "2") (pinfunction "2_2") (pintype "passive"))
      (node (ref "U11") (pin "P$1") (pinfunction "VCC1_P$1") (pintype "bidirectional"))
      (node (ref "U12") (pin "P$16") (pinfunction "VCC2_P$16") (pintype "bidirectional"))
      (node (ref "U14") (pin "20") (pinfunction "VDD_20") (pintype "power_in"))
      (node (ref "U15") (pin "5") (pinfunction "SPLIT/VIO_5") (pintype "bidirectional"))
      (node (ref "U18") (pin "16") (pinfunction "VCC_16") (pintype "power_in"))
      (node (ref "U18") (pin "5") (pinfunction "EN_5") (pintype "input"))
      (node (ref "U19") (pin "14") (pinfunction "VCC_14") (pintype "power_in"))
      (node (ref "U20") (pin "14") (pinfunction "VCC_14") (pintype "power_in"))
      (node (ref "U21") (pin "14") (pinfunction "VCC_14") (pintype "power_in"))
    )
    (net (code "2") (name "+5V") (class "Default")
      (node (ref "C17") (pin "1") (pinfunction "1_1") (pintype "passive"))
      (node (ref "C19") (pin "1") (pinfunction "1_1") (pintype "passive"))
      (node (ref "C20") (pin "1") (pinfunction "1_1") (pintype "passive"))
      (node (ref "C33") (pin "1") (pinfunction "1_1") (pintype "passive"))
      (node (ref "C34") (pin "1") (pinfunction "1_1") (pintype "passive"))
      (node (ref "L2") (pin "P$2") (pinfunction "P$2_P$2") (pintype "bidirectional"))
      (node (ref "LED3") (pin "A") (pinfunction "A_A") (pintype "passive"))
      (node (ref "O1") (pin "8") (pinfunction "VCC2_8") (pintype "bidirectional"))
      (node (ref "R24") (pin "2") (pinfunction "2_2") (pintype "passive"))
      (node (ref "R36") (pin "1") (pinfunction "1_1") (pintype "passive"))
      (node (ref "R37") (pin "1") (pinfunction "1_1") (pintype "passive"))
      (node (ref "R5") (pin "2") (pinfunction "2_2") (pintype "passive"))
      (node (ref "U11") (pin "P$16") (pinfunction "VCC2_P$16") (pintype "bidirectional"))
      (node (ref "U12") (pin "P$1") (pinfunction "VCC1_P$1") (pintype "bidirectional"))
      (node (ref "U3") (pin "1") (pinfunction "VDD_1") (pintype "bidirectional"))
      (node (ref "U8") (pin "1") (pinfunction "VDD_1") (pintype "bidirectional"))
    )
    (net (code "3") (name "+5V{slash}1") (class "Default")
      (node (ref "C22") (pin "1") (pinfunction "1_1") (pintype "passive"))
      (node (ref "C23") (pin "1") (pinfunction "1_1") (pintype "passive"))
      (node (ref "C24") (pin "1") (pinfunction "1_1") (pintype "passive"))
      (node (ref "C27") (pin "1") (pinfunction "1_1") (pintype "passive"))
      (node (ref "H4") (pin "1") (pinfunction "1_1") (pintype "bidirectional"))
      (node (ref "H4") (pin "2") (pinfunction "2_2") (pintype "bidirectional"))
      (node (ref "JP1") (pin "2") (pinfunction "2_2") (pintype "passive"))
      (node (ref "JP1") (pin "4") (pinfunction "4_4") (pintype "passive"))
      (node (ref "L3") (pin "P$2") (pinfunction "P$2_P$2") (pintype "bidirectional"))
      (node (ref "LED2") (pin "A") (pinfunction "A_A") (pintype "passive"))
      (node (ref "R12") (pin "2") (pinfunction "2_2") (pintype "passive"))
      (node (ref "R13") (pin "2") (pinfunction "2_2") (pintype "passive"))
      (node (ref "R15") (pin "2") (pinfunction "2_2") (pintype "passive"))
      (node (ref "R16") (pin "2") (pinfunction "2_2") (pintype "passive"))
      (node (ref "R7") (pin "2") (pinfunction "2_2") (pintype "passive"))
      (node (ref "U15") (pin "3") (pinfunction "VDD_3") (pintype "power_in"))
    )
    (net (code "4") (name "/ACUMULATOR_CONTACTOR_SIGNAL") (class "Default")
      (node (ref "H4") (pin "3") (pinfunction "3_3") (pintype "bidirectional"))
      (node (ref "TP8") (pin "TP") (pinfunction "TP_TP") (pintype "input"))
      (node (ref "U32") (pin "1") (pinfunction "S_1") (pintype "bidirectional"))
      (node (ref "U32") (pin "2") (pinfunction "S_2") (pintype "bidirectional"))
      (node (ref "U32") (pin "3") (pinfunction "S_3") (pintype "bidirectional"))
    )
    (net (code "5") (name "/BSPD_FET_SIGNAL") (class "Default")
      (node (ref "R28") (pin "1") (pinfunction "1_1") (pintype "passive"))
      (node (ref "TP3") (pin "TP") (pinfunction "TP_TP") (pintype "input"))
      (node (ref "U18") (pin "9") (pinfunction "Q_9") (pintype "output"))
      (node (ref "U22") (pin "5") (pinfunction "IN_5") (pintype "input"))
    )
    (net (code "6") (name "/CAN_N") (class "Default")
      (node (ref "H4") (pin "5") (pinfunction "5_5") (pintype "bidirectional"))
      (node (ref "R17") (pin "2") (pinfunction "2_2") (pintype "passive"))
      (node (ref "U15") (pin "6") (pinfunction "CANL_6") (pintype "bidirectional"))
    )
    (net (code "7") (name "/CAN_P") (class "Default")
      (node (ref "H4") (pin "4") (pinfunction "4_4") (pintype "bidirectional"))
      (node (ref "R17") (pin "1") (pinfunction "1_1") (pintype "passive"))
      (node (ref "U15") (pin "7") (pinfunction "CANH_7") (pintype "bidirectional"))
    )
    (net (code "8") (name "/CS_SPI") (class "Default")
      (node (ref "JP1") (pin "24") (pinfunction "24_24") (pintype "passive"))
      (node (ref "TP4") (pin "TP") (pinfunction "TP_TP") (pintype "input"))
      (node (ref "U14") (pin "18") (pinfunction "*CS_18") (pintype "passive"))
    )
    (net (code "9") (name "/DRIVE_DISBALE_SIGNAL_3V3") (class "Default")
      (node (ref "Q11") (pin "S") (pinfunction "S_S") (pintype "bidirectional"))
      (node (ref "R45") (pin "1") (pinfunction "1_1") (pintype "passive"))
      (node (ref "U19") (pin "2") (pinfunction "IN2_2") (pintype "input"))
      (node (ref "U21") (pin "3") (pinfunction "IN_3") (pintype "input"))
    )
    (net (code "10") (name "/HVR_INTERCONNECT_3V3") (class "Default")
      (node (ref "Q9") (pin "S") (pinfunction "S_S") (pintype "bidirectional"))
      (node (ref "R41") (pin "1") (pinfunction "1_1") (pintype "passive"))
      (node (ref "U19") (pin "5") (pinfunction "IN2_5") (pintype "input"))
      (node (ref "U21") (pin "1") (pinfunction "IN_1") (pintype "input"))
    )
    (net (code "11") (name "/IMD_FET_SIGNAL") (class "Default")
      (node (ref "R23") (pin "1") (pinfunction "1_1") (pintype "passive"))
      (node (ref "TP32") (pin "TP") (pinfunction "TP_TP") (pintype "input"))
      (node (ref "U18") (pin "2") (pinfunction "Q_2") (pintype "output"))
      (node (ref "U22") (pin "4") (pinfunction "IN_4") (pintype "input"))
    )
    (net (code "12") (name "/MCU_RESET") (class "Default")
      (node (ref "C39") (pin "1") (pinfunction "1_1") (pintype "passive"))
      (node (ref "R32") (pin "1") (pinfunction "1_1") (pintype "passive"))
      (node (ref "R33") (pin "2") (pinfunction "2_2") (pintype "passive"))
      (node (ref "TP27") (pin "TP") (pinfunction "TP_TP") (pintype "input"))
      (node (ref "U49") (pin "2") (pinfunction "*RESIN_2") (pintype "passive"))
    )
    (net (code "13") (name "/N$49") (class "Default")
      (node (ref "R15") (pin "1") (pinfunction "1_1") (pintype "passive"))
      (node (ref "U14") (pin "13") (pinfunction "*INT_13") (pintype "output"))
    )
    (net (code "14") (name "/N$68") (class "Default")
      (node (ref "R16") (pin "1") (pinfunction "1_1") (pintype "passive"))
      (node (ref "U14") (pin "19") (pinfunction "*RESET_19") (pintype "passive"))
    )
    (net (code "15") (name "/POR") (class "Default")
      (node (ref "TP28") (pin "TP") (pinfunction "TP_TP") (pintype "input"))
      (node (ref "U20") (pin "2") (pinfunction "IN2_2") (pintype "input"))
      (node (ref "U20") (pin "5") (pinfunction "IN2_5") (pintype "input"))
      (node (ref "U20") (pin "9") (pinfunction "IN2_9") (pintype "input"))
      (node (ref "U21") (pin "6") (pinfunction "OUT_6") (pintype "output"))
    )
    (net (code "16") (name "/RSC_SIGNAL_3V3") (class "Default")
      (node (ref "Q10") (pin "S") (pinfunction "S_S") (pintype "bidirectional"))
      (node (ref "R43") (pin "1") (pinfunction "1_1") (pintype "passive"))
      (node (ref "U19") (pin "9") (pinfunction "IN2_9") (pintype "input"))
      (node (ref "U21") (pin "9") (pinfunction "IN_9") (pintype "input"))
    )
    (net (code "17") (name "/RTDS_SIGNAL") (class "Default")
      (node (ref "R29") (pin "1") (pinfunction "1_1") (pintype "passive"))
      (node (ref "TP7") (pin "TP") (pinfunction "TP_TP") (pintype "input"))
      (node (ref "U18") (pin "10") (pinfunction "Q_10") (pintype "output"))
      (node (ref "U27") (pin "4") (pinfunction "IN_4") (pintype "input"))
    )
    (net (code "18") (name "/RTDS_SOURCE") (class "Default")
      (node (ref "TP5") (pin "TP") (pinfunction "TP_TP") (pintype "input"))
      (node (ref "U28") (pin "1") (pinfunction "S_1") (pintype "bidirectional"))
      (node (ref "U28") (pin "2") (pinfunction "S_2") (pintype "bidirectional"))
      (node (ref "U28") (pin "3") (pinfunction "S_3") (pintype "bidirectional"))
      (node (ref "U30") (pin "5") (pinfunction "D_5") (pintype "bidirectional"))
      (node (ref "U30") (pin "6") (pinfunction "D_6") (pintype "bidirectional"))
      (node (ref "U30") (pin "7") (pinfunction "D_7") (pintype "bidirectional"))
      (node (ref "U30") (pin "8") (pinfunction "D_8") (pintype "bidirectional"))
      (node (ref "U30") (pin "PAD") (pinfunction "D_PAD") (pintype "bidirectional"))
      (node (ref "U30") (pin "PAD1") (pinfunction "D_PAD1") (pintype "bidirectional"))
      (node (ref "U30") (pin "VIA1") (pinfunction "D_VIA1") (pintype "bidirectional"))
      (node (ref "U30") (pin "VIA2") (pinfunction "D_VIA2") (pintype "bidirectional"))
      (node (ref "U30") (pin "VIA3") (pinfunction "D_VIA3") (pintype "bidirectional"))
      (node (ref "U30") (pin "VIA4") (pinfunction "D_VIA4") (pintype "bidirectional"))
      (node (ref "U30") (pin "VIA5") (pinfunction "D_VIA5") (pintype "bidirectional"))
      (node (ref "U30") (pin "VIA6") (pinfunction "D_VIA6") (pintype "bidirectional"))
      (node (ref "U30") (pin "VIA7") (pinfunction "D_VIA7") (pintype "bidirectional"))
      (node (ref "U30") (pin "VIA8") (pinfunction "D_VIA8") (pintype "bidirectional"))
      (node (ref "U30") (pin "VIA9") (pinfunction "D_VIA9") (pintype "bidirectional"))
      (node (ref "U32") (pin "5") (pinfunction "D_5") (pintype "bidirectional"))
      (node (ref "U32") (pin "6") (pinfunction "D_6") (pintype "bidirectional"))
      (node (ref "U32") (pin "7") (pinfunction "D_7") (pintype "bidirectional"))
      (node (ref "U32") (pin "8") (pinfunction "D_8") (pintype "bidirectional"))
      (node (ref "U32") (pin "PAD") (pinfunction "D_PAD") (pintype "bidirectional"))
      (node (ref "U32") (pin "PAD1") (pinfunction "D_PAD1") (pintype "bidirectional"))
      (node (ref "U32") (pin "VIA1") (pinfunction "D_VIA1") (pintype "bidirectional"))
      (node (ref "U32") (pin "VIA2") (pinfunction "D_VIA2") (pintype "bidirectional"))
      (node (ref "U32") (pin "VIA3") (pinfunction "D_VIA3") (pintype "bidirectional"))
      (node (ref "U32") (pin "VIA4") (pinfunction "D_VIA4") (pintype "bidirectional"))
      (node (ref "U32") (pin "VIA5") (pinfunction "D_VIA5") (pintype "bidirectional"))
      (node (ref "U32") (pin "VIA6") (pinfunction "D_VIA6") (pintype "bidirectional"))
      (node (ref "U32") (pin "VIA7") (pinfunction "D_VIA7") (pintype "bidirectional"))
      (node (ref "U32") (pin "VIA8") (pinfunction "D_VIA8") (pintype "bidirectional"))
      (node (ref "U32") (pin "VIA9") (pinfunction "D_VIA9") (pintype "bidirectional"))
      (node (ref "U34") (pin "5") (pinfunction "D_5") (pintype "bidirectional"))
      (node (ref "U34") (pin "6") (pinfunction "D_6") (pintype "bidirectional"))
      (node (ref "U34") (pin "7") (pinfunction "D_7") (pintype "bidirectional"))
      (node (ref "U34") (pin "8") (pinfunction "D_8") (pintype "bidirectional"))
      (node (ref "U34") (pin "PAD") (pinfunction "D_PAD") (pintype "bidirectional"))
      (node (ref "U34") (pin "PAD1") (pinfunction "D_PAD1") (pintype "bidirectional"))
      (node (ref "U34") (pin "VIA1") (pinfunction "D_VIA1") (pintype "bidirectional"))
      (node (ref "U34") (pin "VIA2") (pinfunction "D_VIA2") (pintype "bidirectional"))
      (node (ref "U34") (pin "VIA3") (pinfunction "D_VIA3") (pintype "bidirectional"))
      (node (ref "U34") (pin "VIA4") (pinfunction "D_VIA4") (pintype "bidirectional"))
      (node (ref "U34") (pin "VIA5") (pinfunction "D_VIA5") (pintype "bidirectional"))
      (node (ref "U34") (pin "VIA6") (pinfunction "D_VIA6") (pintype "bidirectional"))
      (node (ref "U34") (pin "VIA7") (pinfunction "D_VIA7") (pintype "bidirectional"))
      (node (ref "U34") (pin "VIA8") (pinfunction "D_VIA8") (pintype "bidirectional"))
      (node (ref "U34") (pin "VIA9") (pinfunction "D_VIA9") (pintype "bidirectional"))
    )
    (net (code "19") (name "/SCK_SPI") (class "Default")
      (node (ref "JP1") (pin "23") (pinfunction "23_23") (pintype "passive"))
      (node (ref "TP19") (pin "TP") (pinfunction "TP_TP") (pintype "input"))
      (node (ref "U14") (pin "14") (pinfunction "SCK_14") (pintype "passive"))
    )
    (net (code "20") (name "/SI_SPI") (class "Default")
      (node (ref "JP1") (pin "19") (pinfunction "19_19") (pintype "passive"))
      (node (ref "TP15") (pin "TP") (pinfunction "TP_TP") (pintype "input"))
      (node (ref "U14") (pin "16") (pinfunction "SI_16") (pintype "passive"))
    )
    (net (code "21") (name "/SO_SPI") (class "Default")
      (node (ref "JP1") (pin "21") (pinfunction "21_21") (pintype "passive"))
      (node (ref "TP12") (pin "TP") (pinfunction "TP_TP") (pintype "input"))
      (node (ref "U14") (pin "17") (pinfunction "SO_17") (pintype "passive"))
    )
    (net (code "22") (name "AMS15V") (class "Default")
      (node (ref "H4") (pin "6") (pinfunction "6_6") (pintype "bidirectional"))
      (node (ref "R11") (pin "2") (pinfunction "2_2") (pintype "passive"))
      (node (ref "R18") (pin "2") (pinfunction "2_2") (pintype "passive"))
    )
    (net (code "23") (name "AMS_BACK_TO_PI") (class "Default")
      (node (ref "JP1") (pin "37") (pinfunction "37_37") (pintype "passive"))
      (node (ref "U19") (pin "10") (pinfunction "IN1_10") (pintype "input"))
    )
    (net (code "24") (name "BSPD_FET_SIGNAL1") (class "Default")
      (node (ref "JP1") (pin "33") (pinfunction "33_33") (pintype "passive"))
      (node (ref "TP14") (pin "TP") (pinfunction "TP_TP") (pintype "input"))
      (node (ref "U27") (pin "5") (pinfunction "IN_5") (pintype "input"))
    )
    (net (code "25") (name "BSPD_FET_SIGNAL2") (class "Default")
      (node (ref "JP1") (pin "22") (pinfunction "22_22") (pintype "passive"))
      (node (ref "TP11") (pin "TP") (pinfunction "TP_TP") (pintype "input"))
      (node (ref "U29") (pin "4") (pinfunction "IN_4") (pintype "input"))
    )
    (net (code "26") (name "BSPD_FET_SIGNAL3") (class "Default")
      (node (ref "JP1") (pin "32") (pinfunction "32_32") (pintype "passive"))
      (node (ref "TP18") (pin "TP") (pinfunction "TP_TP") (pintype "input"))
      (node (ref "U29") (pin "5") (pinfunction "IN_5") (pintype "input"))
    )
    (net (code "27") (name "GND") (class "Default")
      (node (ref "C12") (pin "2") (pinfunction "2_2") (pintype "passive"))
      (node (ref "C13") (pin "2") (pinfunction "2_2") (pintype "passive"))
      (node (ref "C14") (pin "2") (pinfunction "2_2") (pintype "passive"))
      (node (ref "C15") (pin "2") (pinfunction "2_2") (pintype "passive"))
      (node (ref "C17") (pin "2") (pinfunction "2_2") (pintype "passive"))
      (node (ref "C19") (pin "2") (pinfunction "2_2") (pintype "passive"))
      (node (ref "C20") (pin "2") (pinfunction "2_2") (pintype "passive"))
      (node (ref "C33") (pin "2") (pinfunction "2_2") (pintype "passive"))
      (node (ref "C34") (pin "2") (pinfunction "2_2") (pintype "passive"))
      (node (ref "H2") (pin "3") (pinfunction "3_3") (pintype "bidirectional"))
      (node (ref "H2") (pin "4") (pinfunction "4_4") (pintype "bidirectional"))
      (node (ref "O1") (pin "5") (pinfunction "GND2_5") (pintype "bidirectional"))
      (node (ref "R25") (pin "1") (pinfunction "1_1") (pintype "passive"))
      (node (ref "R27") (pin "1") (pinfunction "1_1") (pintype "passive"))
      (node (ref "R6") (pin "2") (pinfunction "2_2") (pintype "passive"))
      (node (ref "U10") (pin "1") (pinfunction "GND_1") (pintype "bidirectional"))
      (node (ref "U11") (pin "P$15") (pinfunction "GND2_P$15") (pintype "bidirectional"))
      (node (ref "U11") (pin "P$9") (pinfunction "GND2_P$9") (pintype "bidirectional"))
      (node (ref "U12") (pin "P$2") (pinfunction "GND1_P$2") (pintype "bidirectional"))
      (node (ref "U12") (pin "P$8") (pinfunction "GND1_P$8") (pintype "bidirectional"))
      (node (ref "U3") (pin "2") (pinfunction "GND_2") (pintype "bidirectional"))
      (node (ref "U8") (pin "2") (pinfunction "GND_2") (pintype "bidirectional"))
    )
    (net (code "28") (name "GND1") (class "Default")
      (node (ref "C1") (pin "2") (pinfunction "2_2") (pintype "passive"))
      (node (ref "C10") (pin "2") (pinfunction "2_2") (pintype "passive"))
      (node (ref "C11") (pin "2") (pinfunction "2_2") (pintype "passive"))
      (node (ref "C18") (pin "2") (pinfunction "2_2") (pintype "passive"))
      (node (ref "C2") (pin "2") (pinfunction "2_2") (pintype "passive"))
      (node (ref "C22") (pin "2") (pinfunction "2_2") (pintype "passive"))
      (node (ref "C23") (pin "2") (pinfunction "2_2") (pintype "passive"))
      (node (ref "C24") (pin "2") (pinfunction "2_2") (pintype "passive"))
      (node (ref "C25") (pin "2") (pinfunction "2_2") (pintype "passive"))
      (node (ref "C26") (pin "2") (pinfunction "2_2") (pintype "passive"))
      (node (ref "C27") (pin "2") (pinfunction "2_2") (pintype "passive"))
      (node (ref "C28") (pin "2") (pinfunction "2_2") (pintype "passive"))
      (node (ref "C29") (pin "2") (pinfunction "2_2") (pintype "passive"))
      (node (ref "C3") (pin "2") (pinfunction "2_2") (pintype "passive"))
      (node (ref "C30") (pin "2") (pinfunction "2_2") (pintype "passive"))
      (node (ref "C31") (pin "1") (pinfunction "1_1") (pintype "passive"))
      (node (ref "C32") (pin "1") (pinfunction "1_1") (pintype "passive"))
      (node (ref "C35") (pin "2") (pinfunction "2_2") (pintype "passive"))
      (node (ref "C36") (pin "2") (pinfunction "2_2") (pintype "passive"))
      (node (ref "C37") (pin "2") (pinfunction "2_2") (pintype "passive"))
      (node (ref "C38") (pin "2") (pinfunction "2_2") (pintype "passive"))
      (node (ref "C39") (pin "2") (pinfunction "2_2") (pintype "passive"))
      (node (ref "C4") (pin "2") (pinfunction "2_2") (pintype "passive"))
      (node (ref "C40") (pin "2") (pinfunction "2_2") (pintype "passive"))
      (node (ref "C41") (pin "2") (pinfunction "2_2") (pintype "passive"))
      (node (ref "C42") (pin "2") (pinfunction "2_2") (pintype "passive"))
      (node (ref "C43") (pin "2") (pinfunction "2_2") (pintype "passive"))
      (node (ref "C44") (pin "2") (pinfunction "2_2") (pintype "passive"))
      (node (ref "C45") (pin "2") (pinfunction "2_2") (pintype "passive"))
      (node (ref "C46") (pin "2") (pinfunction "2_2") (pintype "passive"))
      (node (ref "C6") (pin "2") (pinfunction "2_2") (pintype "passive"))
      (node (ref "C7") (pin "2") (pinfunction "2_2") (pintype "passive"))
      (node (ref "C8") (pin "2") (pinfunction "2_2") (pintype "passive"))
      (node (ref "C9") (pin "2") (pinfunction "2_2") (pintype "passive"))
      (node (ref "H4") (pin "10") (pinfunction "10_10") (pintype "bidirectional"))
      (node (ref "H4") (pin "9") (pinfunction "9_9") (pintype "bidirectional"))
      (node (ref "J1") (pin "2") (pinfunction "2_2") (pintype "bidirectional"))
      (node (ref "J2") (pin "1") (pinfunction "1_1") (pintype "bidirectional"))
      (node (ref "J2") (pin "2") (pinfunction "2_2") (pintype "bidirectional"))
      (node (ref "J3") (pin "2") (pinfunction "2_2") (pintype "bidirectional"))
      (node (ref "J4") (pin "2") (pinfunction "2_2") (pintype "bidirectional"))
      (node (ref "J5") (pin "2") (pinfunction "2_2") (pintype "bidirectional"))
      (node (ref "J6") (pin "2") (pinfunction "2_2") (pintype "bidirectional"))
      (node (ref "JP1") (pin "14") (pinfunction "14_14") (pintype "passive"))
      (node (ref "JP1") (pin "20") (pinfunction "20_20") (pintype "passive"))
      (node (ref "JP1") (pin "25") (pinfunction "25_25") (pintype "passive"))
      (node (ref "JP1") (pin "30") (pinfunction "30_30") (pintype "passive"))
      (node (ref "JP1") (pin "34") (pinfunction "34_34") (pintype "passive"))
      (node (ref "JP1") (pin "39") (pinfunction "39_39") (pintype "passive"))
      (node (ref "JP1") (pin "6") (pinfunction "6_6") (pintype "passive"))
      (node (ref "JP1") (pin "9") (pinfunction "9_9") (pintype "passive"))
      (node (ref "O1") (pin "4") (pinfunction "GND1_4") (pintype "bidirectional"))
      (node (ref "R10") (pin "1") (pinfunction "1_1") (pintype "passive"))
      (node (ref "R18") (pin "1") (pinfunction "1_1") (pintype "passive"))
      (node (ref "R2") (pin "1") (pinfunction "1_1") (pintype "passive"))
      (node (ref "R20") (pin "1") (pinfunction "1_1") (pintype "passive"))
      (node (ref "R4") (pin "1") (pinfunction "1_1") (pintype "passive"))
      (node (ref "R8") (pin "1") (pinfunction "1_1") (pintype "passive"))
      (node (ref "S1") (pin "3") (pinfunction "3_3") (pintype "bidirectional"))
      (node (ref "S1") (pin "4") (pinfunction "4_4") (pintype "bidirectional"))
      (node (ref "U11") (pin "P$2") (pinfunction "GND1_P$2") (pintype "bidirectional"))
      (node (ref "U11") (pin "P$8") (pinfunction "GND1_P$8") (pintype "bidirectional"))
      (node (ref "U12") (pin "P$15") (pinfunction "GND2_P$15") (pintype "bidirectional"))
      (node (ref "U12") (pin "P$9") (pinfunction "GND2_P$9") (pintype "bidirectional"))
      (node (ref "U13") (pin "1") (pinfunction "GND_1") (pintype "bidirectional"))
      (node (ref "U14") (pin "10") (pinfunction "VSS_10") (pintype "power_in"))
      (node (ref "U15") (pin "2") (pinfunction "VSS_2") (pintype "power_in"))
      (node (ref "U15") (pin "8") (pinfunction "STBY_8") (pintype "input"))
      (node (ref "U17") (pin "8") (pinfunction "GND_8") (pintype "power_in"))
      (node (ref "U18") (pin "8") (pinfunction "GND_8") (pintype "power_in"))
      (node (ref "U19") (pin "7") (pinfunction "GND_7") (pintype "power_in"))
      (node (ref "U20") (pin "7") (pinfunction "GND_7") (pintype "power_in"))
      (node (ref "U21") (pin "7") (pinfunction "GND_7") (pintype "power_in"))
      (node (ref "U22") (pin "3") (pinfunction "GND_3") (pintype "power_in"))
      (node (ref "U27") (pin "3") (pinfunction "GND_3") (pintype "power_in"))
      (node (ref "U29") (pin "3") (pinfunction "GND_3") (pintype "power_in"))
      (node (ref "U49") (pin "4") (pinfunction "GND_4") (pintype "power_in"))
      (node (ref "U9") (pin "1") (pinfunction "GND_1") (pintype "bidirectional"))
    )
    (net (code "29") (name "IMD15V") (class "Default")
      (node (ref "H4") (pin "7") (pinfunction "7_7") (pintype "bidirectional"))
      (node (ref "R21") (pin "2") (pinfunction "2_2") (pintype "passive"))
      (node (ref "R22") (pin "2") (pinfunction "2_2") (pintype "passive"))
    )
    (net (code "30") (name "IMD_BACK_TO_PI") (class "Default")
      (node (ref "JP1") (pin "40") (pinfunction "40_40") (pintype "passive"))
      (node (ref "U19") (pin "4") (pinfunction "IN1_4") (pintype "input"))
    )
    (net (code "31") (name "INTERUPT15V") (class "Default")
      (node (ref "H4") (pin "8") (pinfunction "8_8") (pintype "bidirectional"))
      (node (ref "R19") (pin "2") (pinfunction "2_2") (pintype "passive"))
      (node (ref "R20") (pin "2") (pinfunction "2_2") (pintype "passive"))
    )
    (net (code "32") (name "INTERUPT_LINES_BACK_TO_PI") (class "Default")
      (node (ref "JP1") (pin "35") (pinfunction "35_35") (pintype "passive"))
      (node (ref "U19") (pin "1") (pinfunction "IN1_1") (pintype "input"))
    )
    (net (code "33") (name "LED_TO_PI_1") (class "Default")
      (node (ref "JP1") (pin "18") (pinfunction "18_18") (pintype "passive"))
      (node (ref "U12") (pin "P$14") (pinfunction "OUTA_P$14") (pintype "bidirectional"))
    )
    (net (code "34") (name "LED_TO_PI_2") (class "Default")
      (node (ref "JP1") (pin "16") (pinfunction "16_16") (pintype "passive"))
      (node (ref "U12") (pin "P$13") (pinfunction "OUTB_P$13") (pintype "bidirectional"))
    )
    (net (code "35") (name "LED_TO_PI_3") (class "Default")
      (node (ref "JP1") (pin "12") (pinfunction "12_12") (pintype "passive"))
      (node (ref "U12") (pin "P$12") (pinfunction "OUTC_P$12") (pintype "bidirectional"))
    )
    (net (code "36") (name "LED_TO_PI_4") (class "Default")
      (node (ref "JP1") (pin "7") (pinfunction "7_7") (pintype "passive"))
      (node (ref "U12") (pin "P$11") (pinfunction "OUTD_P$11") (pintype "bidirectional"))
    )
    (net (code "37") (name "Net-(J1-Pad1)") (class "Default")
      (node (ref "J1") (pin "1") (pinfunction "1_1") (pintype "bidirectional"))
      (node (ref "J3") (pin "1") (pinfunction "1_1") (pintype "bidirectional"))
      (node (ref "TP9") (pin "TP") (pinfunction "TP_TP") (pintype "input"))
      (node (ref "U30") (pin "1") (pinfunction "S_1") (pintype "bidirectional"))
      (node (ref "U30") (pin "2") (pinfunction "S_2") (pintype "bidirectional"))
      (node (ref "U30") (pin "3") (pinfunction "S_3") (pintype "bidirectional"))
    )
    (net (code "38") (name "Net-(J4-Pad1)") (class "Default")
      (node (ref "J4") (pin "1") (pinfunction "1_1") (pintype "bidirectional"))
      (node (ref "J5") (pin "1") (pinfunction "1_1") (pintype "bidirectional"))
      (node (ref "J6") (pin "1") (pinfunction "1_1") (pintype "bidirectional"))
      (node (ref "TP16") (pin "TP") (pinfunction "TP_TP") (pintype "input"))
      (node (ref "U34") (pin "1") (pinfunction "S_1") (pintype "bidirectional"))
      (node (ref "U34") (pin "2") (pinfunction "S_2") (pintype "bidirectional"))
      (node (ref "U34") (pin "3") (pinfunction "S_3") (pintype "bidirectional"))
    )
    (net (code "39") (name "Net-(LED1-PadC)") (class "Default")
      (node (ref "LED1") (pin "C") (pinfunction "C_C") (pintype "passive"))
      (node (ref "R4") (pin "2") (pinfunction "2_2") (pintype "passive"))
    )
    (net (code "40") (name "Net-(LED2-PadC)") (class "Default")
      (node (ref "LED2") (pin "C") (pinfunction "C_C") (pintype "passive"))
      (node (ref "R10") (pin "2") (pinfunction "2_2") (pintype "passive"))
    )
    (net (code "41") (name "Net-(LED3-PadC)") (class "Default")
      (node (ref "LED3") (pin "C") (pinfunction "C_C") (pintype "passive"))
      (node (ref "R27") (pin "2") (pinfunction "2_2") (pintype "passive"))
    )
    (net (code "42") (name "Net-(LED29-PadA)") (class "Default")
      (node (ref "LED29") (pin "A") (pinfunction "A_A") (pintype "passive"))
      (node (ref "R13") (pin "1") (pinfunction "1_1") (pintype "passive"))
    )
    (net (code "43") (name "Net-(LED30-PadA)") (class "Default")
      (node (ref "LED30") (pin "A") (pinfunction "A_A") (pintype "passive"))
      (node (ref "R12") (pin "1") (pinfunction "1_1") (pintype "passive"))
    )
    (net (code "44") (name "Net-(O1-SCL2)") (class "Default")
      (node (ref "O1") (pin "6") (pinfunction "SCL2_6") (pintype "bidirectional"))
      (node (ref "R36") (pin "2") (pinfunction "2_2") (pintype "passive"))
      (node (ref "U3") (pin "4") (pinfunction "SCL_4") (pintype "bidirectional"))
      (node (ref "U8") (pin "4") (pinfunction "SCL_4") (pintype "bidirectional"))
    )
    (net (code "45") (name "Net-(O1-SDA2)") (class "Default")
      (node (ref "O1") (pin "7") (pinfunction "SDA2_7") (pintype "bidirectional"))
      (node (ref "R37") (pin "2") (pinfunction "2_2") (pintype "passive"))
      (node (ref "U3") (pin "3") (pinfunction "SDA_3") (pintype "bidirectional"))
      (node (ref "U8") (pin "3") (pinfunction "SDA_3") (pintype "bidirectional"))
    )
    (net (code "46") (name "Net-(R32-Pad2)") (class "Default")
      (node (ref "R32") (pin "2") (pinfunction "2_2") (pintype "passive"))
      (node (ref "S1") (pin "1") (pinfunction "1_1") (pintype "bidirectional"))
      (node (ref "S1") (pin "2") (pinfunction "2_2") (pintype "bidirectional"))
    )
    (net (code "47") (name "Net-(TP1-PadTP)") (class "Default")
      (node (ref "TP1") (pin "TP") (pinfunction "TP_TP") (pintype "input"))
      (node (ref "U26") (pin "1") (pinfunction "S_1") (pintype "bidirectional"))
      (node (ref "U26") (pin "2") (pinfunction "S_2") (pintype "bidirectional"))
      (node (ref "U26") (pin "3") (pinfunction "S_3") (pintype "bidirectional"))
      (node (ref "U28") (pin "5") (pinfunction "D_5") (pintype "bidirectional"))
      (node (ref "U28") (pin "6") (pinfunction "D_6") (pintype "bidirectional"))
      (node (ref "U28") (pin "7") (pinfunction "D_7") (pintype "bidirectional"))
      (node (ref "U28") (pin "8") (pinfunction "D_8") (pintype "bidirectional"))
      (node (ref "U28") (pin "PAD") (pinfunction "D_PAD") (pintype "bidirectional"))
      (node (ref "U28") (pin "PAD1") (pinfunction "D_PAD1") (pintype "bidirectional"))
      (node (ref "U28") (pin "VIA1") (pinfunction "D_VIA1") (pintype "bidirectional"))
      (node (ref "U28") (pin "VIA2") (pinfunction "D_VIA2") (pintype "bidirectional"))
      (node (ref "U28") (pin "VIA3") (pinfunction "D_VIA3") (pintype "bidirectional"))
      (node (ref "U28") (pin "VIA4") (pinfunction "D_VIA4") (pintype "bidirectional"))
      (node (ref "U28") (pin "VIA5") (pinfunction "D_VIA5") (pintype "bidirectional"))
      (node (ref "U28") (pin "VIA6") (pinfunction "D_VIA6") (pintype "bidirectional"))
      (node (ref "U28") (pin "VIA7") (pinfunction "D_VIA7") (pintype "bidirectional"))
      (node (ref "U28") (pin "VIA8") (pinfunction "D_VIA8") (pintype "bidirectional"))
      (node (ref "U28") (pin "VIA9") (pinfunction "D_VIA9") (pintype "bidirectional"))
    )
    (net (code "48") (name "Net-(TP30-PadTP)") (class "Default")
      (node (ref "TP30") (pin "TP") (pinfunction "TP_TP") (pintype "input"))
      (node (ref "U23") (pin "1") (pinfunction "S_1") (pintype "bidirectional"))
      (node (ref "U23") (pin "2") (pinfunction "S_2") (pintype "bidirectional"))
      (node (ref "U23") (pin "3") (pinfunction "S_3") (pintype "bidirectional"))
      (node (ref "U26") (pin "5") (pinfunction "D_5") (pintype "bidirectional"))
      (node (ref "U26") (pin "6") (pinfunction "D_6") (pintype "bidirectional"))
      (node (ref "U26") (pin "7") (pinfunction "D_7") (pintype "bidirectional"))
      (node (ref "U26") (pin "8") (pinfunction "D_8") (pintype "bidirectional"))
      (node (ref "U26") (pin "PAD") (pinfunction "D_PAD") (pintype "bidirectional"))
      (node (ref "U26") (pin "PAD1") (pinfunction "D_PAD1") (pintype "bidirectional"))
      (node (ref "U26") (pin "VIA1") (pinfunction "D_VIA1") (pintype "bidirectional"))
      (node (ref "U26") (pin "VIA2") (pinfunction "D_VIA2") (pintype "bidirectional"))
      (node (ref "U26") (pin "VIA3") (pinfunction "D_VIA3") (pintype "bidirectional"))
      (node (ref "U26") (pin "VIA4") (pinfunction "D_VIA4") (pintype "bidirectional"))
      (node (ref "U26") (pin "VIA5") (pinfunction "D_VIA5") (pintype "bidirectional"))
      (node (ref "U26") (pin "VIA6") (pinfunction "D_VIA6") (pintype "bidirectional"))
      (node (ref "U26") (pin "VIA7") (pinfunction "D_VIA7") (pintype "bidirectional"))
      (node (ref "U26") (pin "VIA8") (pinfunction "D_VIA8") (pintype "bidirectional"))
      (node (ref "U26") (pin "VIA9") (pinfunction "D_VIA9") (pintype "bidirectional"))
    )
    (net (code "49") (name "Net-(U3-ADD)") (class "Default")
      (node (ref "R6") (pin "1") (pinfunction "1_1") (pintype "passive"))
      (node (ref "U3") (pin "5") (pinfunction "ADD_5") (pintype "bidirectional"))
    )
    (net (code "50") (name "Net-(U3-OUT)") (class "Default")
      (node (ref "H2") (pin "7") (pinfunction "7_7") (pintype "bidirectional"))
      (node (ref "U3") (pin "6") (pinfunction "OUT_6") (pintype "bidirectional"))
    )
    (net (code "51") (name "Net-(U8-ADD)") (class "Default")
      (node (ref "R5") (pin "1") (pinfunction "1_1") (pintype "passive"))
      (node (ref "U8") (pin "5") (pinfunction "ADD_5") (pintype "bidirectional"))
    )
    (net (code "52") (name "Net-(U8-OUT)") (class "Default")
      (node (ref "H2") (pin "8") (pinfunction "8_8") (pintype "bidirectional"))
      (node (ref "U8") (pin "6") (pinfunction "OUT_6") (pintype "bidirectional"))
    )
    (net (code "53") (name "Net-(U9-EN)") (class "Default")
      (node (ref "R3") (pin "2") (pinfunction "2_2") (pintype "passive"))
      (node (ref "U9") (pin "7") (pinfunction "EN_7") (pintype "bidirectional"))
    )
    (net (code "54") (name "Net-(U9-SS)") (class "Default")
      (node (ref "C4") (pin "1") (pinfunction "1_1") (pintype "passive"))
      (node (ref "U9") (pin "5") (pinfunction "SS_5") (pintype "bidirectional"))
    )
    (net (code "55") (name "Net-(U9-SW)") (class "Default")
      (node (ref "C5") (pin "2") (pinfunction "2_2") (pintype "passive"))
      (node (ref "L1") (pin "P$1") (pinfunction "P$1_P$1") (pintype "bidirectional"))
      (node (ref "U9") (pin "2") (pinfunction "SW_2") (pintype "bidirectional"))
    )
    (net (code "56") (name "Net-(U9-VBST)") (class "Default")
      (node (ref "C5") (pin "1") (pinfunction "1_1") (pintype "passive"))
      (node (ref "U9") (pin "8") (pinfunction "VBST_8") (pintype "bidirectional"))
    )
    (net (code "57") (name "Net-(U9-VFB)") (class "Default")
      (node (ref "R1") (pin "1") (pinfunction "1_1") (pintype "passive"))
      (node (ref "R2") (pin "2") (pinfunction "2_2") (pintype "passive"))
      (node (ref "U9") (pin "6") (pinfunction "VFB_6") (pintype "bidirectional"))
    )
    (net (code "58") (name "Net-(U10-EN)") (class "Default")
      (node (ref "R26") (pin "2") (pinfunction "2_2") (pintype "passive"))
      (node (ref "U10") (pin "7") (pinfunction "EN_7") (pintype "bidirectional"))
    )
    (net (code "59") (name "Net-(U10-SS)") (class "Default")
      (node (ref "C15") (pin "1") (pinfunction "1_1") (pintype "passive"))
      (node (ref "U10") (pin "5") (pinfunction "SS_5") (pintype "bidirectional"))
    )
    (net (code "60") (name "Net-(U10-SW)") (class "Default")
      (node (ref "C16") (pin "2") (pinfunction "2_2") (pintype "passive"))
      (node (ref "L2") (pin "P$1") (pinfunction "P$1_P$1") (pintype "bidirectional"))
      (node (ref "U10") (pin "2") (pinfunction "SW_2") (pintype "bidirectional"))
    )
    (net (code "61") (name "Net-(U10-VBST)") (class "Default")
      (node (ref "C16") (pin "1") (pinfunction "1_1") (pintype "passive"))
      (node (ref "U10") (pin "8") (pinfunction "VBST_8") (pintype "bidirectional"))
    )
    (net (code "62") (name "Net-(U10-VFB)") (class "Default")
      (node (ref "R24") (pin "1") (pinfunction "1_1") (pintype "passive"))
      (node (ref "R25") (pin "2") (pinfunction "2_2") (pintype "passive"))
      (node (ref "U10") (pin "6") (pinfunction "VFB_6") (pintype "bidirectional"))
    )
    (net (code "63") (name "Net-(U11-OUTA)") (class "Default")
      (node (ref "H3") (pin "5") (pinfunction "5_5") (pintype "bidirectional"))
      (node (ref "U11") (pin "P$14") (pinfunction "OUTA_P$14") (pintype "bidirectional"))
    )
    (net (code "64") (name "Net-(U11-OUTB)") (class "Default")
      (node (ref "H3") (pin "6") (pinfunction "6_6") (pintype "bidirectional"))
      (node (ref "U11") (pin "P$13") (pinfunction "OUTB_P$13") (pintype "bidirectional"))
    )
    (net (code "65") (name "Net-(U11-OUTC)") (class "Default")
      (node (ref "H3") (pin "7") (pinfunction "7_7") (pintype "bidirectional"))
      (node (ref "U11") (pin "P$12") (pinfunction "OUTC_P$12") (pintype "bidirectional"))
    )
    (net (code "66") (name "Net-(U11-OUTD)") (class "Default")
      (node (ref "H3") (pin "8") (pinfunction "8_8") (pintype "bidirectional"))
      (node (ref "U11") (pin "P$11") (pinfunction "OUTD_P$11") (pintype "bidirectional"))
    )
    (net (code "67") (name "Net-(U12-INA)") (class "Default")
      (node (ref "H3") (pin "4") (pinfunction "4_4") (pintype "bidirectional"))
      (node (ref "U12") (pin "P$3") (pinfunction "INA_P$3") (pintype "bidirectional"))
    )
    (net (code "68") (name "Net-(U12-INB)") (class "Default")
      (node (ref "H3") (pin "3") (pinfunction "3_3") (pintype "bidirectional"))
      (node (ref "U12") (pin "P$4") (pinfunction "INB_P$4") (pintype "bidirectional"))
    )
    (net (code "69") (name "Net-(U12-INC)") (class "Default")
      (node (ref "H3") (pin "2") (pinfunction "2_2") (pintype "bidirectional"))
      (node (ref "U12") (pin "P$5") (pinfunction "INC_P$5") (pintype "bidirectional"))
    )
    (net (code "70") (name "Net-(U12-IND)") (class "Default")
      (node (ref "H3") (pin "1") (pinfunction "1_1") (pintype "bidirectional"))
      (node (ref "U12") (pin "P$6") (pinfunction "IND_P$6") (pintype "bidirectional"))
    )
    (net (code "71") (name "Net-(U13-EN)") (class "Default")
      (node (ref "R9") (pin "2") (pinfunction "2_2") (pintype "passive"))
      (node (ref "U13") (pin "7") (pinfunction "EN_7") (pintype "bidirectional"))
    )
    (net (code "72") (name "Net-(U13-SS)") (class "Default")
      (node (ref "C18") (pin "1") (pinfunction "1_1") (pintype "passive"))
      (node (ref "U13") (pin "5") (pinfunction "SS_5") (pintype "bidirectional"))
    )
    (net (code "73") (name "Net-(U13-SW)") (class "Default")
      (node (ref "C21") (pin "2") (pinfunction "2_2") (pintype "passive"))
      (node (ref "L3") (pin "P$1") (pinfunction "P$1_P$1") (pintype "bidirectional"))
      (node (ref "U13") (pin "2") (pinfunction "SW_2") (pintype "bidirectional"))
    )
    (net (code "74") (name "Net-(U13-VBST)") (class "Default")
      (node (ref "C21") (pin "1") (pinfunction "1_1") (pintype "passive"))
      (node (ref "U13") (pin "8") (pinfunction "VBST_8") (pintype "bidirectional"))
    )
    (net (code "75") (name "Net-(U13-VFB)") (class "Default")
      (node (ref "R7") (pin "1") (pinfunction "1_1") (pintype "passive"))
      (node (ref "R8") (pin "2") (pinfunction "2_2") (pintype "passive"))
      (node (ref "U13") (pin "6") (pinfunction "VFB_6") (pintype "bidirectional"))
    )
    (net (code "76") (name "Net-(U14-*RX0BF)") (class "Default")
      (node (ref "LED29") (pin "C") (pinfunction "C_C") (pintype "passive"))
      (node (ref "U14") (pin "12") (pinfunction "*RX0BF_12") (pintype "passive"))
    )
    (net (code "77") (name "Net-(U14-*RX1BF)") (class "Default")
      (node (ref "LED30") (pin "C") (pinfunction "C_C") (pintype "passive"))
      (node (ref "U14") (pin "11") (pinfunction "*RX1BF_11") (pintype "passive"))
    )
    (net (code "78") (name "Net-(U14-OSC1)") (class "Default")
      (node (ref "C25") (pin "1") (pinfunction "1_1") (pintype "passive"))
      (node (ref "U14") (pin "9") (pinfunction "OSC1_9") (pintype "passive"))
      (node (ref "Y1") (pin "P$2") (pinfunction "P$3_P$2") (pintype "bidirectional"))
    )
    (net (code "79") (name "Net-(U14-OSC2)") (class "Default")
      (node (ref "C26") (pin "1") (pinfunction "1_1") (pintype "passive"))
      (node (ref "U14") (pin "8") (pinfunction "OSC2_8") (pintype "passive"))
      (node (ref "Y1") (pin "P$1") (pinfunction "P$1_P$1") (pintype "bidirectional"))
    )
    (net (code "80") (name "Net-(U14-RXCAN)") (class "Default")
      (node (ref "U14") (pin "2") (pinfunction "RXCAN_2") (pintype "passive"))
      (node (ref "U15") (pin "4") (pinfunction "RXD_4") (pintype "bidirectional"))
    )
    (net (code "81") (name "Net-(U14-TXCAN)") (class "Default")
      (node (ref "U14") (pin "1") (pinfunction "TXCAN_1") (pintype "passive"))
      (node (ref "U15") (pin "1") (pinfunction "TXD_1") (pintype "bidirectional"))
    )
    (net (code "82") (name "Net-(U17A-IN)") (class "Default")
      (node (ref "C30") (pin "1") (pinfunction "1_1") (pintype "passive"))
      (node (ref "R21") (pin "1") (pinfunction "1_1") (pintype "passive"))
      (node (ref "U17") (pin "3") (pinfunction "IN_3") (pintype "input"))
    )
    (net (code "83") (name "Net-(U17A-OUT)") (class "Default")
      (node (ref "Q9") (pin "D") (pinfunction "D_D") (pintype "bidirectional"))
      (node (ref "U17") (pin "2") (pinfunction "OUT_2") (pintype "output"))
    )
    (net (code "84") (name "Net-(U17B-IN)") (class "Default")
      (node (ref "C28") (pin "1") (pinfunction "1_1") (pintype "passive"))
      (node (ref "R11") (pin "1") (pinfunction "1_1") (pintype "passive"))
      (node (ref "U17") (pin "5") (pinfunction "IN_5") (pintype "input"))
    )
    (net (code "85") (name "Net-(U17B-OUT)") (class "Default")
      (node (ref "Q10") (pin "D") (pinfunction "D_D") (pintype "bidirectional"))
      (node (ref "U17") (pin "4") (pinfunction "OUT_4") (pintype "output"))
    )
    (net (code "86") (name "Net-(U17C-IN)") (class "Default")
      (node (ref "C29") (pin "1") (pinfunction "1_1") (pintype "passive"))
      (node (ref "R19") (pin "1") (pinfunction "1_1") (pintype "passive"))
      (node (ref "U17") (pin "7") (pinfunction "IN_7") (pintype "input"))
    )
    (net (code "87") (name "Net-(U17C-OUT)") (class "Default")
      (node (ref "Q11") (pin "D") (pinfunction "D_D") (pintype "bidirectional"))
      (node (ref "U17") (pin "6") (pinfunction "OUT_6") (pintype "output"))
    )
    (net (code "88") (name "Net-(U18A-R)") (class "Default")
      (node (ref "U18") (pin "3") (pinfunction "R_3") (pintype "input"))
      (node (ref "U20") (pin "6") (pinfunction "OUT_6") (pintype "output"))
    )
    (net (code "89") (name "Net-(U18A-S)") (class "Default")
      (node (ref "U18") (pin "4") (pinfunction "S_4") (pintype "input"))
      (node (ref "U19") (pin "6") (pinfunction "OUT_6") (pintype "output"))
    )
    (net (code "90") (name "Net-(U18B-R)") (class "Default")
      (node (ref "U18") (pin "7") (pinfunction "R_7") (pintype "input"))
      (node (ref "U20") (pin "8") (pinfunction "OUT_8") (pintype "output"))
    )
    (net (code "91") (name "Net-(U18B-S)") (class "Default")
      (node (ref "U18") (pin "6") (pinfunction "S_6") (pintype "input"))
      (node (ref "U19") (pin "8") (pinfunction "OUT_8") (pintype "output"))
    )
    (net (code "92") (name "Net-(U18C-R)") (class "Default")
      (node (ref "U18") (pin "11") (pinfunction "R_11") (pintype "input"))
      (node (ref "U20") (pin "3") (pinfunction "OUT_3") (pintype "output"))
    )
    (net (code "93") (name "Net-(U18C-S)") (class "Default")
      (node (ref "U18") (pin "12") (pinfunction "S_12") (pintype "input"))
      (node (ref "U19") (pin "3") (pinfunction "OUT_3") (pintype "output"))
    )
    (net (code "94") (name "Net-(U20A-IN1)") (class "Default")
      (node (ref "U20") (pin "1") (pinfunction "IN1_1") (pintype "input"))
      (node (ref "U21") (pin "4") (pinfunction "OUT_4") (pintype "output"))
    )
    (net (code "95") (name "Net-(U20B-IN1)") (class "Default")
      (node (ref "U20") (pin "4") (pinfunction "IN1_4") (pintype "input"))
      (node (ref "U21") (pin "2") (pinfunction "OUT_2") (pintype "output"))
    )
    (net (code "96") (name "Net-(U20C-IN1)") (class "Default")
      (node (ref "U20") (pin "10") (pinfunction "IN1_10") (pintype "input"))
      (node (ref "U21") (pin "8") (pinfunction "OUT_8") (pintype "output"))
    )
    (net (code "97") (name "Net-(U21C-IN)") (class "Default")
      (node (ref "Q8") (pin "S") (pinfunction "S_S") (pintype "bidirectional"))
      (node (ref "R31") (pin "1") (pinfunction "1_1") (pintype "passive"))
      (node (ref "U21") (pin "5") (pinfunction "IN_5") (pintype "input"))
    )
    (net (code "98") (name "Net-(U22A-G)") (class "Default")
      (node (ref "TP31") (pin "TP") (pinfunction "TP_TP") (pintype "input"))
      (node (ref "U22") (pin "2") (pinfunction "G_2") (pintype "output"))
      (node (ref "U23") (pin "4") (pinfunction "G_4") (pintype "input"))
    )
    (net (code "99") (name "Net-(U22B-G)") (class "Default")
      (node (ref "TP2") (pin "TP") (pinfunction "TP_TP") (pintype "input"))
      (node (ref "U22") (pin "7") (pinfunction "G_7") (pintype "output"))
      (node (ref "U26") (pin "4") (pinfunction "G_4") (pintype "input"))
    )
    (net (code "100") (name "Net-(U27A-G)") (class "Default")
      (node (ref "TP6") (pin "TP") (pinfunction "TP_TP") (pintype "input"))
      (node (ref "U27") (pin "2") (pinfunction "G_2") (pintype "output"))
      (node (ref "U28") (pin "4") (pinfunction "G_4") (pintype "input"))
    )
    (net (code "101") (name "Net-(U27B-G)") (class "Default")
      (node (ref "TP13") (pin "TP") (pinfunction "TP_TP") (pintype "input"))
      (node (ref "U27") (pin "7") (pinfunction "G_7") (pintype "output"))
      (node (ref "U32") (pin "4") (pinfunction "G_4") (pintype "input"))
    )
    (net (code "102") (name "Net-(U29A-G)") (class "Default")
      (node (ref "TP10") (pin "TP") (pinfunction "TP_TP") (pintype "input"))
      (node (ref "U29") (pin "2") (pinfunction "G_2") (pintype "output"))
      (node (ref "U30") (pin "4") (pinfunction "G_4") (pintype "input"))
    )
    (net (code "103") (name "Net-(U29B-G)") (class "Default")
      (node (ref "TP17") (pin "TP") (pinfunction "TP_TP") (pintype "input"))
      (node (ref "U29") (pin "7") (pinfunction "G_7") (pintype "output"))
      (node (ref "U34") (pin "4") (pinfunction "G_4") (pintype "input"))
    )
    (net (code "104") (name "Net-(U49-*RESET)") (class "Default")
      (node (ref "Q8") (pin "D") (pinfunction "D_D") (pintype "bidirectional"))
      (node (ref "R30") (pin "1") (pinfunction "1_1") (pintype "passive"))
      (node (ref "TP26") (pin "TP") (pinfunction "TP_TP") (pintype "input"))
      (node (ref "U49") (pin "5") (pinfunction "*RESET_5") (pintype "passive"))
    )
    (net (code "105") (name "Net-(U49-CT)") (class "Default")
      (node (ref "C31") (pin "2") (pinfunction "2_2") (pintype "passive"))
      (node (ref "U49") (pin "3") (pinfunction "CT_3") (pintype "passive"))
    )
    (net (code "106") (name "Net-(U49-REF)") (class "Default")
      (node (ref "C32") (pin "2") (pinfunction "2_2") (pintype "passive"))
      (node (ref "U49") (pin "1") (pinfunction "REF_1") (pintype "passive"))
    )
    (net (code "107") (name "SCL1_I2C") (class "Default")
      (node (ref "JP1") (pin "3") (pinfunction "3_3") (pintype "passive"))
      (node (ref "O1") (pin "3") (pinfunction "SCL1_3") (pintype "bidirectional"))
      (node (ref "R35") (pin "2") (pinfunction "2_2") (pintype "passive"))
    )
    (net (code "108") (name "SDA1_I2C") (class "Default")
      (node (ref "JP1") (pin "5") (pinfunction "5_5") (pintype "passive"))
      (node (ref "O1") (pin "2") (pinfunction "SDA1_2") (pintype "bidirectional"))
      (node (ref "R34") (pin "2") (pinfunction "2_2") (pintype "passive"))
    )
    (net (code "109") (name "TIMER_ADJ_1") (class "Default")
      (node (ref "JP1") (pin "31") (pinfunction "31_31") (pintype "passive"))
      (node (ref "U11") (pin "P$3") (pinfunction "INA_P$3") (pintype "bidirectional"))
    )
    (net (code "110") (name "TIMER_ADJ_2") (class "Default")
      (node (ref "JP1") (pin "29") (pinfunction "29_29") (pintype "passive"))
      (node (ref "U11") (pin "P$4") (pinfunction "INB_P$4") (pintype "bidirectional"))
    )
    (net (code "111") (name "TIMER_ADJ_3") (class "Default")
      (node (ref "JP1") (pin "15") (pinfunction "15_15") (pintype "passive"))
      (node (ref "U11") (pin "P$5") (pinfunction "INC_P$5") (pintype "bidirectional"))
    )
    (net (code "112") (name "TIMER_ADJ_4") (class "Default")
      (node (ref "JP1") (pin "13") (pinfunction "13_13") (pintype "passive"))
      (node (ref "U11") (pin "P$6") (pinfunction "IND_P$6") (pintype "bidirectional"))
    )
    (net (code "113") (name "VCC") (class "Default")
      (node (ref "C12") (pin "1") (pinfunction "1_1") (pintype "passive"))
      (node (ref "C13") (pin "1") (pinfunction "1_1") (pintype "passive"))
      (node (ref "C14") (pin "1") (pinfunction "1_1") (pintype "passive"))
      (node (ref "H2") (pin "1") (pinfunction "1_1") (pintype "bidirectional"))
      (node (ref "H2") (pin "2") (pinfunction "2_2") (pintype "bidirectional"))
      (node (ref "R26") (pin "1") (pinfunction "1_1") (pintype "passive"))
      (node (ref "U10") (pin "3") (pinfunction "VIN_3") (pintype "bidirectional"))
    )
    (net (code "114") (name "VDD") (class "Default")
      (node (ref "C1") (pin "1") (pinfunction "1_1") (pintype "passive"))
      (node (ref "C10") (pin "1") (pinfunction "1_1") (pintype "passive"))
      (node (ref "C11") (pin "1") (pinfunction "1_1") (pintype "passive"))
      (node (ref "C2") (pin "1") (pinfunction "1_1") (pintype "passive"))
      (node (ref "C3") (pin "1") (pinfunction "1_1") (pintype "passive"))
      (node (ref "C40") (pin "1") (pinfunction "1_1") (pintype "passive"))
      (node (ref "C43") (pin "1") (pinfunction "1_1") (pintype "passive"))
      (node (ref "C44") (pin "1") (pinfunction "1_1") (pintype "passive"))
      (node (ref "C45") (pin "1") (pinfunction "1_1") (pintype "passive"))
      (node (ref "C46") (pin "1") (pinfunction "1_1") (pintype "passive"))
      (node (ref "C9") (pin "1") (pinfunction "1_1") (pintype "passive"))
      (node (ref "J2") (pin "3") (pinfunction "3_3") (pintype "bidirectional"))
      (node (ref "J2") (pin "4") (pinfunction "4_4") (pintype "bidirectional"))
      (node (ref "R22") (pin "1") (pinfunction "1_1") (pintype "passive"))
      (node (ref "R3") (pin "1") (pinfunction "1_1") (pintype "passive"))
      (node (ref "R30") (pin "2") (pinfunction "2_2") (pintype "passive"))
      (node (ref "R9") (pin "1") (pinfunction "1_1") (pintype "passive"))
      (node (ref "U13") (pin "3") (pinfunction "VIN_3") (pintype "bidirectional"))
      (node (ref "U17") (pin "1") (pinfunction "VCC_1") (pintype "power_in"))
      (node (ref "U22") (pin "1") (pinfunction "D_1") (pintype "input"))
      (node (ref "U22") (pin "6") (pinfunction "VCC_6") (pintype "power_in"))
      (node (ref "U22") (pin "8") (pinfunction "D_8") (pintype "input"))
      (node (ref "U23") (pin "5") (pinfunction "D_5") (pintype "bidirectional"))
      (node (ref "U23") (pin "6") (pinfunction "D_6") (pintype "bidirectional"))
      (node (ref "U23") (pin "7") (pinfunction "D_7") (pintype "bidirectional"))
      (node (ref "U23") (pin "8") (pinfunction "D_8") (pintype "bidirectional"))
      (node (ref "U23") (pin "PAD") (pinfunction "D_PAD") (pintype "bidirectional"))
      (node (ref "U23") (pin "PAD1") (pinfunction "D_PAD1") (pintype "bidirectional"))
      (node (ref "U23") (pin "VIA1") (pinfunction "D_VIA1") (pintype "bidirectional"))
      (node (ref "U23") (pin "VIA2") (pinfunction "D_VIA2") (pintype "bidirectional"))
      (node (ref "U23") (pin "VIA3") (pinfunction "D_VIA3") (pintype "bidirectional"))
      (node (ref "U23") (pin "VIA4") (pinfunction "D_VIA4") (pintype "bidirectional"))
      (node (ref "U23") (pin "VIA5") (pinfunction "D_VIA5") (pintype "bidirectional"))
      (node (ref "U23") (pin "VIA6") (pinfunction "D_VIA6") (pintype "bidirectional"))
      (node (ref "U23") (pin "VIA7") (pinfunction "D_VIA7") (pintype "bidirectional"))
      (node (ref "U23") (pin "VIA8") (pinfunction "D_VIA8") (pintype "bidirectional"))
      (node (ref "U23") (pin "VIA9") (pinfunction "D_VIA9") (pintype "bidirectional"))
      (node (ref "U27") (pin "1") (pinfunction "D_1") (pintype "input"))
      (node (ref "U27") (pin "6") (pinfunction "VCC_6") (pintype "power_in"))
      (node (ref "U27") (pin "8") (pinfunction "D_8") (pintype "input"))
      (node (ref "U29") (pin "1") (pinfunction "D_1") (pintype "input"))
      (node (ref "U29") (pin "6") (pinfunction "VCC_6") (pintype "power_in"))
      (node (ref "U29") (pin "8") (pinfunction "D_8") (pintype "input"))
      (node (ref "U49") (pin "7") (pinfunction "SENSE_7") (pintype "passive"))
      (node (ref "U49") (pin "8") (pinfunction "VCC_8") (pintype "power_in"))
      (node (ref "U9") (pin "3") (pinfunction "VIN_3") (pintype "bidirectional"))
    )
    (net (code "115") (name "unconnected-(H2-Pad5)") (class "Default")
      (node (ref "H2") (pin "5") (pinfunction "5_5") (pintype "bidirectional"))
    )
    (net (code "116") (name "unconnected-(H2-Pad6)") (class "Default")
      (node (ref "H2") (pin "6") (pinfunction "6_6") (pintype "bidirectional"))
    )
    (net (code "117") (name "unconnected-(JP1-Pad1)") (class "Default")
      (node (ref "JP1") (pin "1") (pinfunction "1_1") (pintype "passive"))
    )
    (net (code "118") (name "unconnected-(JP1-Pad8)") (class "Default")
      (node (ref "JP1") (pin "8") (pinfunction "8_8") (pintype "passive"))
    )
    (net (code "119") (name "unconnected-(JP1-Pad10)") (class "Default")
      (node (ref "JP1") (pin "10") (pinfunction "10_10") (pintype "passive"))
    )
    (net (code "120") (name "unconnected-(JP1-Pad11)") (class "Default")
      (node (ref "JP1") (pin "11") (pinfunction "11_11") (pintype "passive"))
    )
    (net (code "121") (name "unconnected-(JP1-Pad17)") (class "Default")
      (node (ref "JP1") (pin "17") (pinfunction "17_17") (pintype "passive"))
    )
    (net (code "122") (name "unconnected-(JP1-Pad26)") (class "Default")
      (node (ref "JP1") (pin "26") (pinfunction "26_26") (pintype "passive"))
    )
    (net (code "123") (name "unconnected-(JP1-Pad27)") (class "Default")
      (node (ref "JP1") (pin "27") (pinfunction "27_27") (pintype "passive"))
    )
    (net (code "124") (name "unconnected-(JP1-Pad28)") (class "Default")
      (node (ref "JP1") (pin "28") (pinfunction "28_28") (pintype "passive"))
    )
    (net (code "125") (name "unconnected-(JP1-Pad36)") (class "Default")
      (node (ref "JP1") (pin "36") (pinfunction "36_36") (pintype "passive"))
    )
    (net (code "126") (name "unconnected-(JP1-Pad38)") (class "Default")
      (node (ref "JP1") (pin "38") (pinfunction "38_38") (pintype "passive"))
    )
    (net (code "127") (name "unconnected-(U9-PGOOD-Pad4)") (class "Default")
      (node (ref "U9") (pin "4") (pinfunction "PGOOD_4") (pintype "bidirectional"))
    )
    (net (code "128") (name "unconnected-(U10-PGOOD-Pad4)") (class "Default")
      (node (ref "U10") (pin "4") (pinfunction "PGOOD_4") (pintype "bidirectional"))
    )
    (net (code "129") (name "unconnected-(U11-EN-PadP$10)") (class "Default")
      (node (ref "U11") (pin "P$10") (pinfunction "EN_P$10") (pintype "bidirectional"))
    )
    (net (code "130") (name "unconnected-(U12-EN-PadP$10)") (class "Default")
      (node (ref "U12") (pin "P$10") (pinfunction "EN_P$10") (pintype "bidirectional"))
    )
    (net (code "131") (name "unconnected-(U13-PGOOD-Pad4)") (class "Default")
      (node (ref "U13") (pin "4") (pinfunction "PGOOD_4") (pintype "bidirectional"))
    )
    (net (code "132") (name "unconnected-(U14-*TX0RTS-Pad4)") (class "Default")
      (node (ref "U14") (pin "4") (pinfunction "*TX0RTS_4") (pintype "passive"))
    )
    (net (code "133") (name "unconnected-(U14-*TX1RTS-Pad5)") (class "Default")
      (node (ref "U14") (pin "5") (pinfunction "*TX1RTS_5") (pintype "passive"))
    )
    (net (code "134") (name "unconnected-(U14-*TX2RTS-Pad7)") (class "Default")
      (node (ref "U14") (pin "7") (pinfunction "*TX2RTS_7") (pintype "passive"))
    )
    (net (code "135") (name "unconnected-(U14-CLKOUT{slash}SOF-Pad3)") (class "Default")
      (node (ref "U14") (pin "3") (pinfunction "CLKOUT/SOF_3") (pintype "output"))
    )
    (net (code "136") (name "unconnected-(U49-RESET-Pad6)") (class "Default")
      (node (ref "U49") (pin "6") (pinfunction "RESET_6") (pintype "passive"))
    )
  )
)
